# EasyCheck_rev1.net
KiCad netlist of a schematic drawn in EAGLE
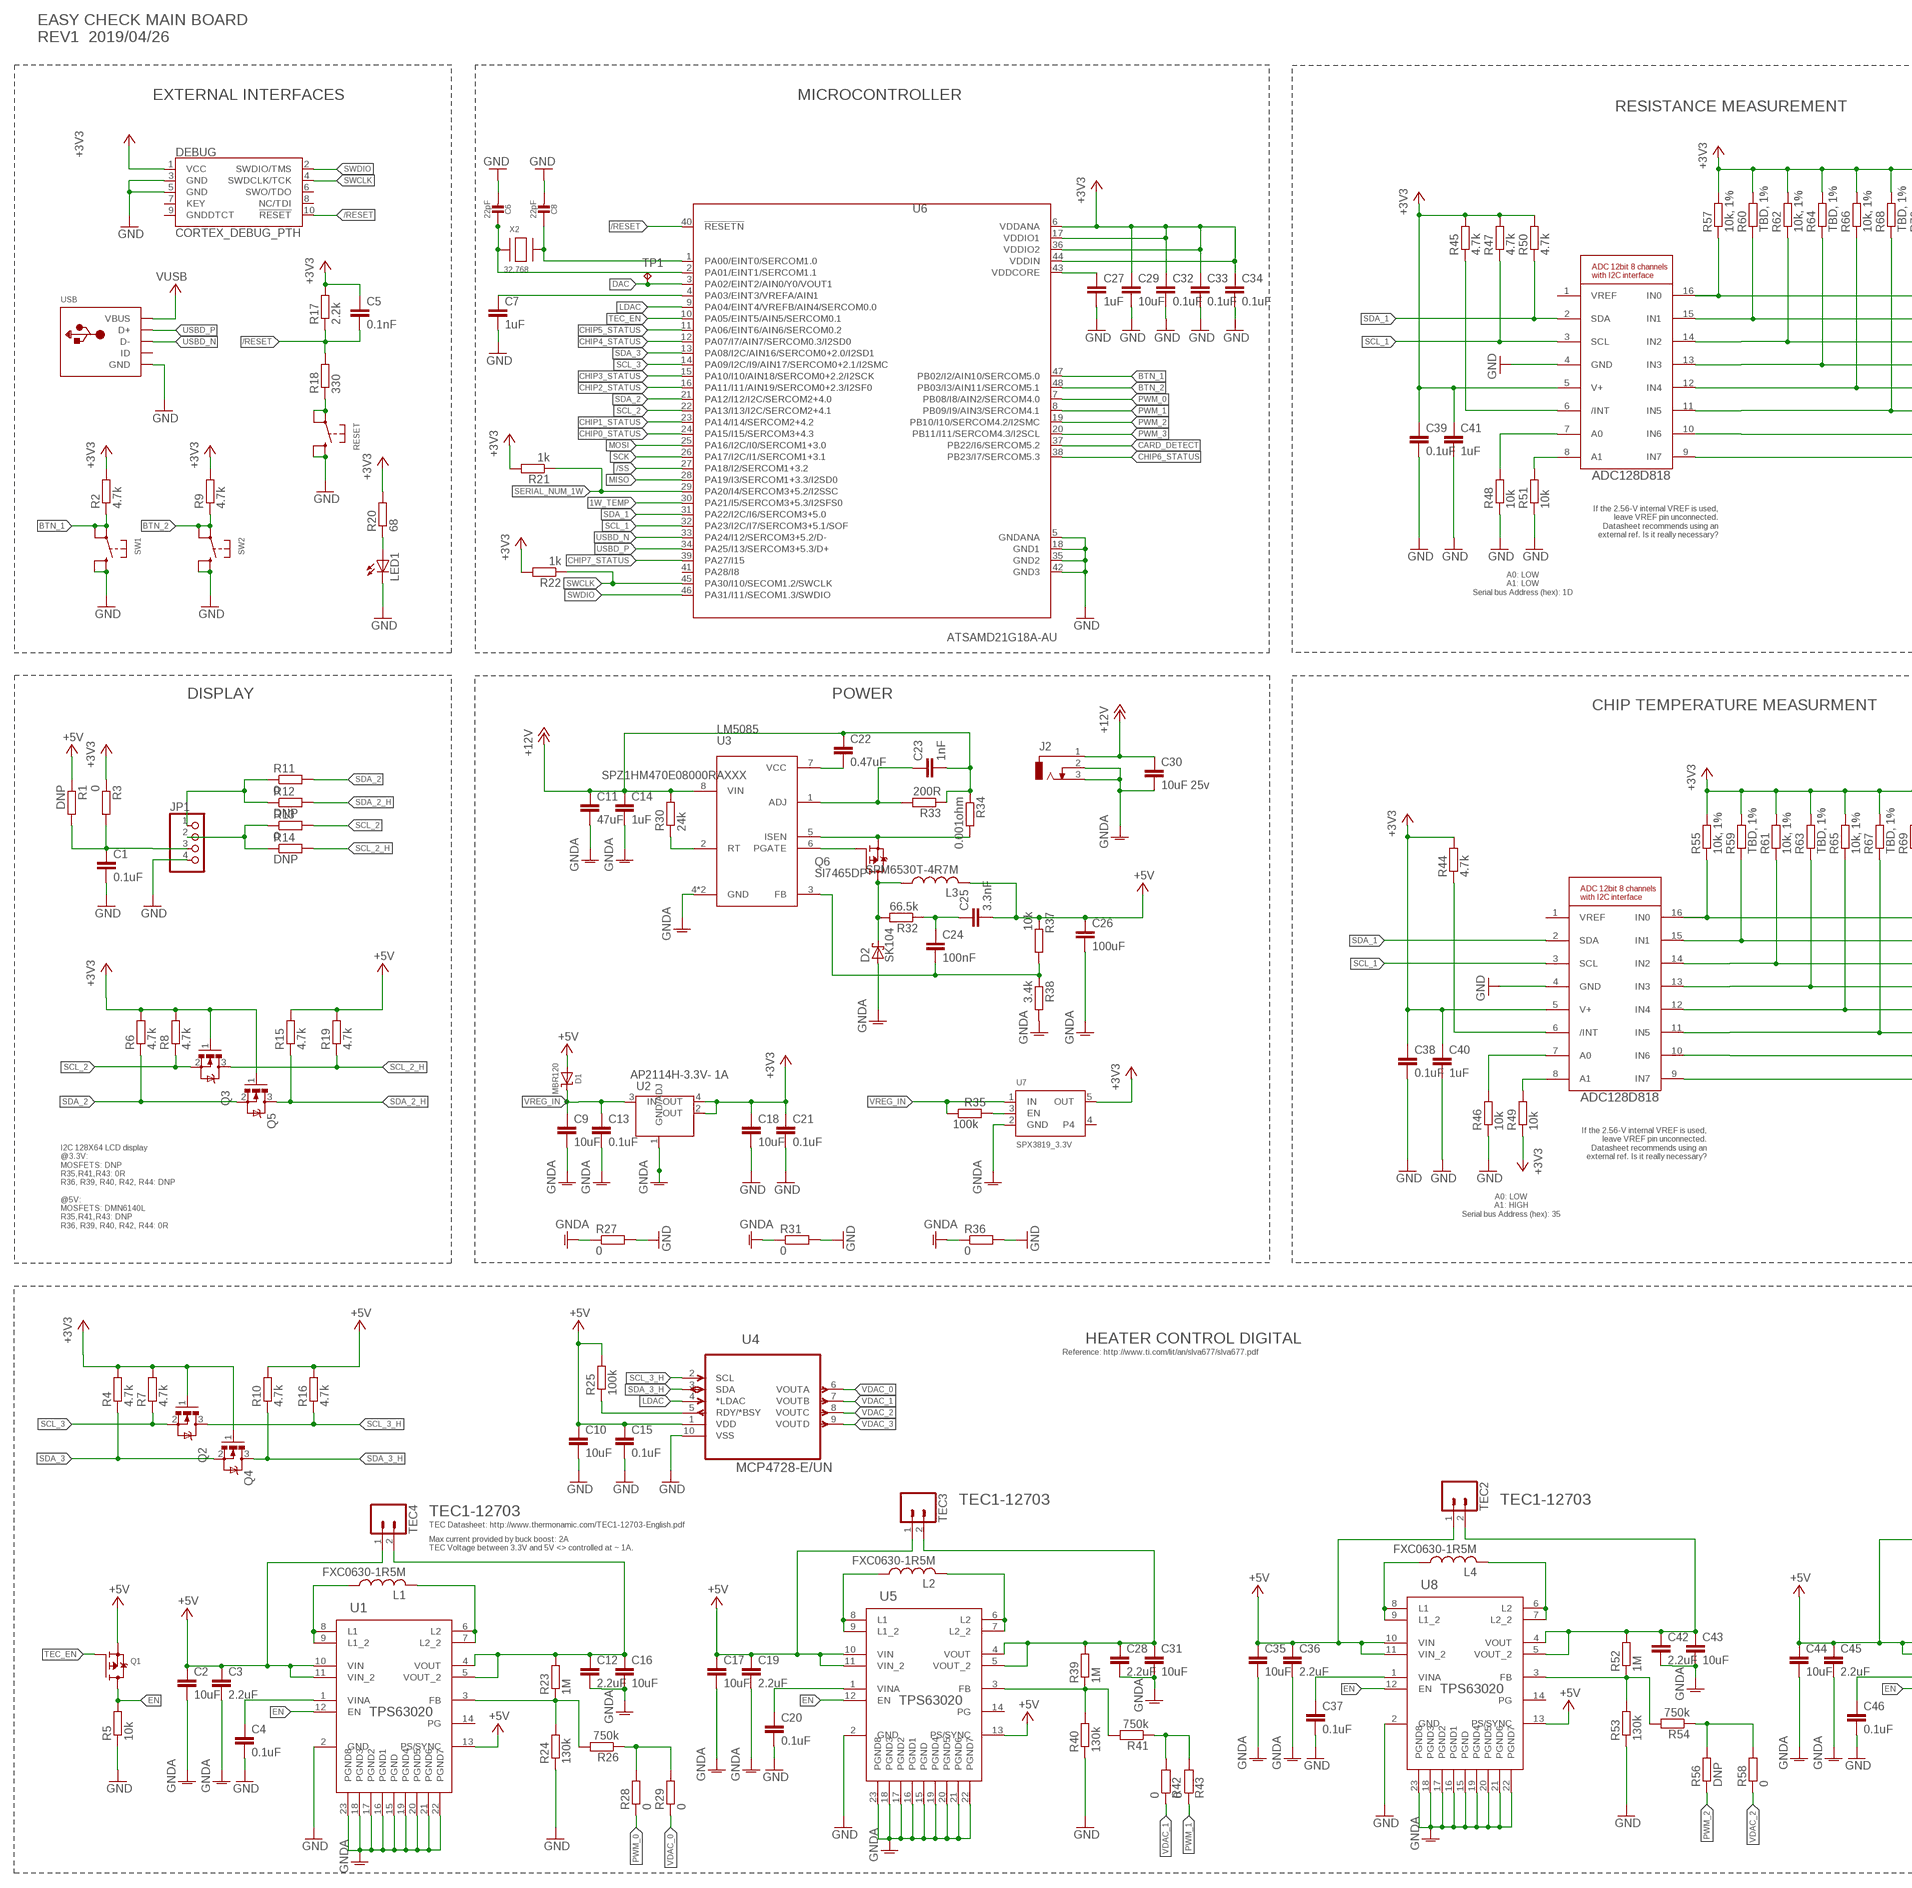
[diagram p0: schematic, sheet 1, part 1 of 2]
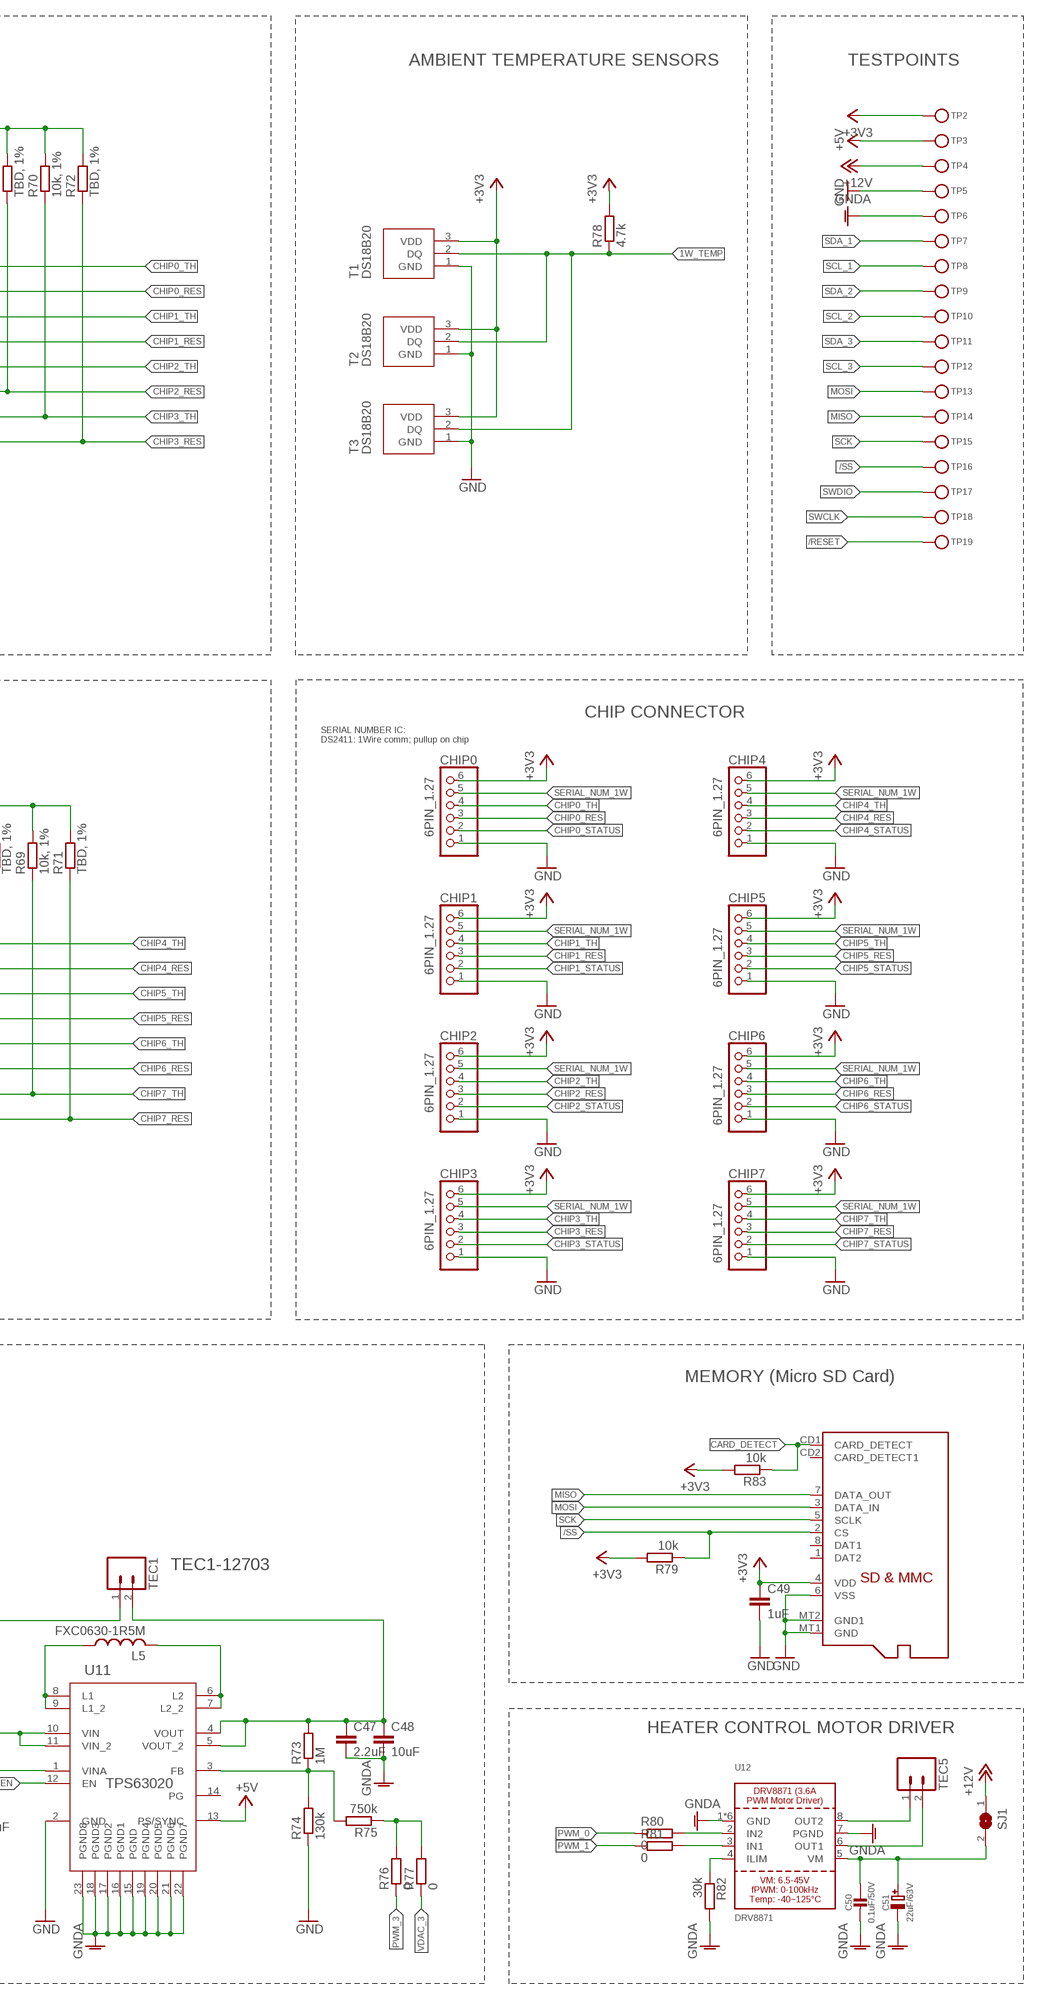
[diagram p1: schematic, sheet 1, part 2 of 2]

(export (version "E")
  (design (tool "Eeschema 10.0.6"))
  (components
    (comp (ref "C1")
      (value "0.1uF")
      (footprint "eagle-import:C0603")
      (libsource (lib "eagle-import") (part "C-EUC0603"))
    )
    (comp (ref "C2")
      (value "10uF")
      (footprint "eagle-import:C0805")
      (libsource (lib "eagle-import") (part "C-EUC0805"))
    )
    (comp (ref "C3")
      (value "2.2uF")
      (footprint "eagle-import:C0805")
      (libsource (lib "eagle-import") (part "C-EUC0805"))
    )
    (comp (ref "C4")
      (value "0.1uF")
      (footprint "eagle-import:C0603")
      (libsource (lib "eagle-import") (part "C-EUC0603"))
    )
    (comp (ref "C5")
      (value "0.1nF")
      (footprint "eagle-import:C0603")
      (libsource (lib "eagle-import") (part "C-EUC0603"))
    )
    (comp (ref "C6")
      (value "22pF")
      (footprint "eagle-import:0603-NO")
      (libsource (lib "eagle-import") (part "CAP_CERAMIC0603_NO"))
    )
    (comp (ref "C7")
      (value "1uF")
      (footprint "eagle-import:C0603")
      (libsource (lib "eagle-import") (part "C-EUC0603"))
    )
    (comp (ref "C8")
      (value "22pF")
      (footprint "eagle-import:0603-NO")
      (libsource (lib "eagle-import") (part "CAP_CERAMIC0603_NO"))
    )
    (comp (ref "C9")
      (value "10uF")
      (footprint "eagle-import:C0603")
      (libsource (lib "eagle-import") (part "C-EUC0603"))
    )
    (comp (ref "C10")
      (value "10uF")
      (footprint "eagle-import:C0603")
      (libsource (lib "eagle-import") (part "C-EUC0603"))
    )
    (comp (ref "C11")
      (value "47uF")
      (footprint "eagle-import:C1206")
      (libsource (lib "eagle-import") (part "C-EUC1206"))
    )
    (comp (ref "C12")
      (value "2.2uF")
      (footprint "eagle-import:C0805")
      (libsource (lib "eagle-import") (part "C-EUC0805"))
    )
    (comp (ref "C13")
      (value "0.1uF")
      (footprint "eagle-import:C0603")
      (libsource (lib "eagle-import") (part "C-EUC0603"))
    )
    (comp (ref "C14")
      (value "1uF")
      (footprint "eagle-import:C1206")
      (libsource (lib "eagle-import") (part "C-EUC1206"))
    )
    (comp (ref "C15")
      (value "0.1uF")
      (footprint "eagle-import:C0603")
      (libsource (lib "eagle-import") (part "C-EUC0603"))
    )
    (comp (ref "C16")
      (value "10uF")
      (footprint "eagle-import:C0805")
      (libsource (lib "eagle-import") (part "C-EUC0805"))
    )
    (comp (ref "C17")
      (value "10uF")
      (footprint "eagle-import:C0805")
      (libsource (lib "eagle-import") (part "C-EUC0805"))
    )
    (comp (ref "C18")
      (value "10uF")
      (footprint "eagle-import:C0603")
      (libsource (lib "eagle-import") (part "C-EUC0603"))
    )
    (comp (ref "C19")
      (value "2.2uF")
      (footprint "eagle-import:C0805")
      (libsource (lib "eagle-import") (part "C-EUC0805"))
    )
    (comp (ref "C20")
      (value "0.1uF")
      (footprint "eagle-import:C0603")
      (libsource (lib "eagle-import") (part "C-EUC0603"))
    )
    (comp (ref "C21")
      (value "0.1uF")
      (footprint "eagle-import:C0603")
      (libsource (lib "eagle-import") (part "C-EUC0603"))
    )
    (comp (ref "C22")
      (value "0.47uF")
      (footprint "eagle-import:C1206")
      (libsource (lib "eagle-import") (part "C-EUC1206"))
    )
    (comp (ref "C23")
      (value "1nF")
      (footprint "eagle-import:C0603")
      (libsource (lib "eagle-import") (part "C-EUC0603"))
    )
    (comp (ref "C24")
      (value "100nF")
      (footprint "eagle-import:C0603")
      (libsource (lib "eagle-import") (part "C-EUC0603"))
    )
    (comp (ref "C25")
      (value "3.3nF")
      (footprint "eagle-import:C0603")
      (libsource (lib "eagle-import") (part "C-EUC0603"))
    )
    (comp (ref "C26")
      (value "100uF")
      (footprint "eagle-import:C1206")
      (libsource (lib "eagle-import") (part "C-EUC1206"))
    )
    (comp (ref "C27")
      (value "1uF")
      (footprint "eagle-import:C0603")
      (libsource (lib "eagle-import") (part "C-EUC0603"))
    )
    (comp (ref "C28")
      (value "2.2uF")
      (footprint "eagle-import:C0805")
      (libsource (lib "eagle-import") (part "C-EUC0805"))
    )
    (comp (ref "C29")
      (value "10uF")
      (footprint "eagle-import:C0603")
      (libsource (lib "eagle-import") (part "C-EUC0603"))
    )
    (comp (ref "C30")
      (value "10uF 25v")
      (footprint "eagle-import:C1206")
      (libsource (lib "eagle-import") (part "C-EUC1206"))
    )
    (comp (ref "C31")
      (value "10uF")
      (footprint "eagle-import:C0805")
      (libsource (lib "eagle-import") (part "C-EUC0805"))
    )
    (comp (ref "C32")
      (value "0.1uF")
      (footprint "eagle-import:C0603")
      (libsource (lib "eagle-import") (part "C-EUC0603"))
    )
    (comp (ref "C33")
      (value "0.1uF")
      (footprint "eagle-import:C0603")
      (libsource (lib "eagle-import") (part "C-EUC0603"))
    )
    (comp (ref "C34")
      (value "0.1uF")
      (footprint "eagle-import:C0603")
      (libsource (lib "eagle-import") (part "C-EUC0603"))
    )
    (comp (ref "C35")
      (value "10uF")
      (footprint "eagle-import:C0603")
      (libsource (lib "eagle-import") (part "C-EUC0603"))
    )
    (comp (ref "C36")
      (value "2.2uF")
      (footprint "eagle-import:C0603")
      (libsource (lib "eagle-import") (part "C-EUC0603"))
    )
    (comp (ref "C37")
      (value "0.1uF")
      (footprint "eagle-import:C0603")
      (libsource (lib "eagle-import") (part "C-EUC0603"))
    )
    (comp (ref "C38")
      (value "0.1uF")
      (footprint "eagle-import:C0603")
      (libsource (lib "eagle-import") (part "C-EUC0603"))
    )
    (comp (ref "C39")
      (value "0.1uF")
      (footprint "eagle-import:C0603")
      (libsource (lib "eagle-import") (part "C-EUC0603"))
    )
    (comp (ref "C40")
      (value "1uF")
      (footprint "eagle-import:C0603")
      (libsource (lib "eagle-import") (part "C-EUC0603"))
    )
    (comp (ref "C41")
      (value "1uF")
      (footprint "eagle-import:C0603")
      (libsource (lib "eagle-import") (part "C-EUC0603"))
    )
    (comp (ref "C42")
      (value "2.2uF")
      (footprint "eagle-import:C0805")
      (libsource (lib "eagle-import") (part "C-EUC0805"))
    )
    (comp (ref "C43")
      (value "10uF")
      (footprint "eagle-import:C0805")
      (libsource (lib "eagle-import") (part "C-EUC0805"))
    )
    (comp (ref "C44")
      (value "10uF")
      (footprint "eagle-import:C0805")
      (libsource (lib "eagle-import") (part "C-EUC0805"))
    )
    (comp (ref "C45")
      (value "2.2uF")
      (footprint "eagle-import:C0805")
      (libsource (lib "eagle-import") (part "C-EUC0805"))
    )
    (comp (ref "C46")
      (value "0.1uF")
      (footprint "eagle-import:C0603")
      (libsource (lib "eagle-import") (part "C-EUC0603"))
    )
    (comp (ref "C47")
      (value "2.2uF")
      (footprint "eagle-import:C0805")
      (libsource (lib "eagle-import") (part "C-EUC0805"))
    )
    (comp (ref "C48")
      (value "10uF")
      (footprint "eagle-import:C0805")
      (libsource (lib "eagle-import") (part "C-EUC0805"))
    )
    (comp (ref "C49")
      (value "1uF")
      (footprint "eagle-import:C0603")
      (libsource (lib "eagle-import") (part "C-EUC0603"))
    )
    (comp (ref "C50")
      (value "0.1uF/50V")
      (footprint "eagle-import:0805-NO")
      (libsource (lib "eagle-import") (part "CAP_CERAMIC0805-NOOUTLINE"))
    )
    (comp (ref "C51")
      (value "22uF/63V")
      (footprint "eagle-import:PANASONIC_D")
      (libsource (lib "eagle-import") (part "CAP_ELECTROLYTICPANASONIC_D"))
    )
    (comp (ref "CHIP0")
      (value "6PIN_1.27")
      (footprint "eagle-import:6X1PIN_1.27")
      (libsource (lib "eagle-import") (part "6PIN_1.27"))
    )
    (comp (ref "CHIP1")
      (value "6PIN_1.27")
      (footprint "eagle-import:6X1PIN_1.27")
      (libsource (lib "eagle-import") (part "6PIN_1.27"))
    )
    (comp (ref "CHIP2")
      (value "6PIN_1.27")
      (footprint "eagle-import:6X1PIN_1.27")
      (libsource (lib "eagle-import") (part "6PIN_1.27"))
    )
    (comp (ref "CHIP3")
      (value "6PIN_1.27")
      (footprint "eagle-import:6X1PIN_1.27")
      (libsource (lib "eagle-import") (part "6PIN_1.27"))
    )
    (comp (ref "CHIP4")
      (value "6PIN_1.27")
      (footprint "eagle-import:6X1PIN_1.27")
      (libsource (lib "eagle-import") (part "6PIN_1.27"))
    )
    (comp (ref "CHIP5")
      (value "6PIN_1.27")
      (footprint "eagle-import:6X1PIN_1.27")
      (libsource (lib "eagle-import") (part "6PIN_1.27"))
    )
    (comp (ref "CHIP6")
      (value "6PIN_1.27")
      (footprint "eagle-import:6X1PIN_1.27")
      (libsource (lib "eagle-import") (part "6PIN_1.27"))
    )
    (comp (ref "CHIP7")
      (value "6PIN_1.27")
      (footprint "eagle-import:6X1PIN_1.27")
      (libsource (lib "eagle-import") (part "6PIN_1.27"))
    )
    (comp (ref "D1")
      (value "MBR120")
      (footprint "eagle-import:MICROBUILDER_SOD-123")
      (libsource (lib "eagle-import") (part "MICROBUILDER_DIODE-SCHOTTKYSOD-123"))
    )
    (comp (ref "D2")
      (value "SK104")
      (footprint "eagle-import:SK104")
      (libsource (lib "eagle-import") (part "SK104"))
    )
    (comp (ref "DEBUG")
      (value "CORTEX_DEBUG_PTH")
      (footprint "eagle-import:2X5-PTH-1.27MM")
      (libsource (lib "eagle-import") (part "CORTEX_DEBUG_PTH"))
    )
    (comp (ref "J2")
      (value "DCJ0303")
      (footprint "eagle-import:DCJ0303")
      (libsource (lib "eagle-import") (part "DCJ0303"))
    )
    (comp (ref "JP1")
      (value "PINHD-1X4")
      (footprint "eagle-import:1X04")
      (libsource (lib "eagle-import") (part "PINHD-1X4"))
    )
    (comp (ref "L1")
      (value "FXC0630-1R5M")
      (footprint "eagle-import:PIS2816")
      (libsource (lib "eagle-import") (part "L-USPIS2816"))
    )
    (comp (ref "L2")
      (value "FXC0630-1R5M")
      (footprint "eagle-import:PIS2816")
      (libsource (lib "eagle-import") (part "L-USPIS2816"))
    )
    (comp (ref "L3")
      (value "SPM6530T-4R7M")
      (footprint "eagle-import:SPM6530T-4R7M")
      (libsource (lib "eagle-import") (part "SPM6530T-4R7M"))
    )
    (comp (ref "L4")
      (value "FXC0630-1R5M")
      (footprint "eagle-import:PIS2816")
      (libsource (lib "eagle-import") (part "L-USPIS2816"))
    )
    (comp (ref "L5")
      (value "FXC0630-1R5M")
      (footprint "eagle-import:PIS2816")
      (libsource (lib "eagle-import") (part "L-USPIS2816"))
    )
    (comp (ref "LED1")
      (value "LEDCHIPLED_0603")
      (footprint "eagle-import:CHIPLED_0603")
      (libsource (lib "eagle-import") (part "LEDCHIPLED_0603"))
    )
    (comp (ref "Q1")
      (value "MICROBUILDER_MOSFET-P")
      (footprint "eagle-import:MICROBUILDER_SOT23-R")
      (libsource (lib "eagle-import") (part "MICROBUILDER_MOSFET-P"))
    )
    (comp (ref "Q2")
      (value "DMN6140L")
      (footprint "eagle-import:SOT91P240X110-3N")
      (libsource (lib "eagle-import") (part "DMN6140L"))
    )
    (comp (ref "Q3")
      (value "DMN6140L")
      (footprint "eagle-import:SOT91P240X110-3N")
      (libsource (lib "eagle-import") (part "DMN6140L"))
    )
    (comp (ref "Q4")
      (value "DMN6140L")
      (footprint "eagle-import:SOT91P240X110-3N")
      (libsource (lib "eagle-import") (part "DMN6140L"))
    )
    (comp (ref "Q5")
      (value "DMN6140L")
      (footprint "eagle-import:SOT91P240X110-3N")
      (libsource (lib "eagle-import") (part "DMN6140L"))
    )
    (comp (ref "Q6")
      (value "SI7465DP")
      (footprint "eagle-import:SI7465")
      (libsource (lib "eagle-import") (part "SI7465DP"))
    )
    (comp (ref "R1")
      (value "DNP")
      (footprint "eagle-import:R0603")
      (libsource (lib "eagle-import") (part "R-EU_R0603"))
    )
    (comp (ref "R2")
      (value "4.7k")
      (footprint "eagle-import:R0603")
      (libsource (lib "eagle-import") (part "R-EU_R0603"))
    )
    (comp (ref "R3")
      (value "0")
      (footprint "eagle-import:R0603")
      (libsource (lib "eagle-import") (part "R-EU_R0603"))
    )
    (comp (ref "R4")
      (value "4.7k")
      (footprint "eagle-import:R0603")
      (libsource (lib "eagle-import") (part "R-EU_R0603"))
    )
    (comp (ref "R5")
      (value "10k")
      (footprint "eagle-import:R0603")
      (libsource (lib "eagle-import") (part "R-EU_R0603"))
    )
    (comp (ref "R6")
      (value "4.7k")
      (footprint "eagle-import:R0603")
      (libsource (lib "eagle-import") (part "R-EU_R0603"))
    )
    (comp (ref "R7")
      (value "4.7k")
      (footprint "eagle-import:R0603")
      (libsource (lib "eagle-import") (part "R-EU_R0603"))
    )
    (comp (ref "R8")
      (value "4.7k")
      (footprint "eagle-import:R0603")
      (libsource (lib "eagle-import") (part "R-EU_R0603"))
    )
    (comp (ref "R9")
      (value "4.7k")
      (footprint "eagle-import:R0603")
      (libsource (lib "eagle-import") (part "R-EU_R0603"))
    )
    (comp (ref "R10")
      (value "4.7k")
      (footprint "eagle-import:R0603")
      (libsource (lib "eagle-import") (part "R-EU_R0603"))
    )
    (comp (ref "R11")
      (value "0")
      (footprint "eagle-import:R0603")
      (libsource (lib "eagle-import") (part "R-EU_R0603"))
    )
    (comp (ref "R12")
      (value "DNP")
      (footprint "eagle-import:R0603")
      (libsource (lib "eagle-import") (part "R-EU_R0603"))
    )
    (comp (ref "R13")
      (value "0")
      (footprint "eagle-import:R0603")
      (libsource (lib "eagle-import") (part "R-EU_R0603"))
    )
    (comp (ref "R14")
      (value "DNP")
      (footprint "eagle-import:R0603")
      (libsource (lib "eagle-import") (part "R-EU_R0603"))
    )
    (comp (ref "R15")
      (value "4.7k")
      (footprint "eagle-import:R0603")
      (libsource (lib "eagle-import") (part "R-EU_R0603"))
    )
    (comp (ref "R16")
      (value "4.7k")
      (footprint "eagle-import:R0603")
      (libsource (lib "eagle-import") (part "R-EU_R0603"))
    )
    (comp (ref "R17")
      (value "2.2k")
      (footprint "eagle-import:R0603")
      (libsource (lib "eagle-import") (part "R-EU_R0603"))
    )
    (comp (ref "R18")
      (value "330")
      (footprint "eagle-import:R0603")
      (libsource (lib "eagle-import") (part "R-EU_R0603"))
    )
    (comp (ref "R19")
      (value "4.7k")
      (footprint "eagle-import:R0603")
      (libsource (lib "eagle-import") (part "R-EU_R0603"))
    )
    (comp (ref "R20")
      (value "68")
      (footprint "eagle-import:R0603")
      (libsource (lib "eagle-import") (part "R-EU_R0603"))
    )
    (comp (ref "R21")
      (value "1k")
      (footprint "eagle-import:R0603")
      (libsource (lib "eagle-import") (part "R-EU_R0603"))
    )
    (comp (ref "R22")
      (value "1k")
      (footprint "eagle-import:R0603")
      (libsource (lib "eagle-import") (part "R-EU_R0603"))
    )
    (comp (ref "R23")
      (value "1M")
      (footprint "eagle-import:R0603")
      (libsource (lib "eagle-import") (part "R-EU_R0603"))
    )
    (comp (ref "R24")
      (value "130k")
      (footprint "eagle-import:R0603")
      (libsource (lib "eagle-import") (part "R-EU_R0603"))
    )
    (comp (ref "R25")
      (value "100k")
      (footprint "eagle-import:R0603")
      (libsource (lib "eagle-import") (part "R-EU_R0603"))
    )
    (comp (ref "R26")
      (value "750k")
      (footprint "eagle-import:R0603")
      (libsource (lib "eagle-import") (part "R-EU_R0603"))
    )
    (comp (ref "R27")
      (value "0")
      (footprint "eagle-import:R0603")
      (libsource (lib "eagle-import") (part "R-EU_R0603"))
    )
    (comp (ref "R28")
      (value "0")
      (footprint "eagle-import:R0603")
      (libsource (lib "eagle-import") (part "R-EU_R0603"))
    )
    (comp (ref "R29")
      (value "0")
      (footprint "eagle-import:R0603")
      (libsource (lib "eagle-import") (part "R-EU_R0603"))
    )
    (comp (ref "R30")
      (value "24k")
      (footprint "eagle-import:R0603")
      (libsource (lib "eagle-import") (part "R-EU_R0603"))
    )
    (comp (ref "R31")
      (value "0")
      (footprint "eagle-import:R0603")
      (libsource (lib "eagle-import") (part "R-EU_R0603"))
    )
    (comp (ref "R32")
      (value "66.5k")
      (footprint "eagle-import:R0603")
      (libsource (lib "eagle-import") (part "R-EU_R0603"))
    )
    (comp (ref "R33")
      (value "200R")
      (footprint "eagle-import:R0603")
      (libsource (lib "eagle-import") (part "R-EU_R0603"))
    )
    (comp (ref "R34")
      (value "0.001ohm")
      (footprint "eagle-import:R1206")
      (libsource (lib "eagle-import") (part "R-EU_R1206"))
    )
    (comp (ref "R35")
      (value "100k")
      (footprint "eagle-import:R0603")
      (libsource (lib "eagle-import") (part "R-EU_R0603"))
    )
    (comp (ref "R36")
      (value "0")
      (footprint "eagle-import:R0603")
      (libsource (lib "eagle-import") (part "R-EU_R0603"))
    )
    (comp (ref "R37")
      (value "10k")
      (footprint "eagle-import:R0603")
      (libsource (lib "eagle-import") (part "R-EU_R0603"))
    )
    (comp (ref "R38")
      (value "3.4k")
      (footprint "eagle-import:R0603")
      (libsource (lib "eagle-import") (part "R-EU_R0603"))
    )
    (comp (ref "R39")
      (value "1M")
      (footprint "eagle-import:R0603")
      (libsource (lib "eagle-import") (part "R-EU_R0603"))
    )
    (comp (ref "R40")
      (value "130k")
      (footprint "eagle-import:R0603")
      (libsource (lib "eagle-import") (part "R-EU_R0603"))
    )
    (comp (ref "R41")
      (value "750k")
      (footprint "eagle-import:R0603")
      (libsource (lib "eagle-import") (part "R-EU_R0603"))
    )
    (comp (ref "R42")
      (value "0")
      (footprint "eagle-import:R0603")
      (libsource (lib "eagle-import") (part "R-EU_R0603"))
    )
    (comp (ref "R43")
      (value "0")
      (footprint "eagle-import:R0603")
      (libsource (lib "eagle-import") (part "R-EU_R0603"))
    )
    (comp (ref "R44")
      (value "4.7k")
      (footprint "eagle-import:R0603")
      (libsource (lib "eagle-import") (part "R-EU_R0603"))
    )
    (comp (ref "R45")
      (value "4.7k")
      (footprint "eagle-import:R0603")
      (libsource (lib "eagle-import") (part "R-EU_R0603"))
    )
    (comp (ref "R46")
      (value "10k")
      (footprint "eagle-import:R0603")
      (libsource (lib "eagle-import") (part "R-EU_R0603"))
    )
    (comp (ref "R47")
      (value "4.7k")
      (footprint "eagle-import:R0603")
      (libsource (lib "eagle-import") (part "R-EU_R0603"))
    )
    (comp (ref "R48")
      (value "10k")
      (footprint "eagle-import:R0603")
      (libsource (lib "eagle-import") (part "R-EU_R0603"))
    )
    (comp (ref "R49")
      (value "10k")
      (footprint "eagle-import:R0603")
      (libsource (lib "eagle-import") (part "R-EU_R0603"))
    )
    (comp (ref "R50")
      (value "4.7k")
      (footprint "eagle-import:R0603")
      (libsource (lib "eagle-import") (part "R-EU_R0603"))
    )
    (comp (ref "R51")
      (value "10k")
      (footprint "eagle-import:R0603")
      (libsource (lib "eagle-import") (part "R-EU_R0603"))
    )
    (comp (ref "R52")
      (value "1M")
      (footprint "eagle-import:R0603")
      (libsource (lib "eagle-import") (part "R-EU_R0603"))
    )
    (comp (ref "R53")
      (value "130k")
      (footprint "eagle-import:R0603")
      (libsource (lib "eagle-import") (part "R-EU_R0603"))
    )
    (comp (ref "R54")
      (value "750k")
      (footprint "eagle-import:R0603")
      (libsource (lib "eagle-import") (part "R-EU_R0603"))
    )
    (comp (ref "R55")
      (value "10k, 1%")
      (footprint "eagle-import:R0603")
      (libsource (lib "eagle-import") (part "R-EU_R0603"))
    )
    (comp (ref "R56")
      (value "DNP")
      (footprint "eagle-import:R0603")
      (libsource (lib "eagle-import") (part "R-EU_R0603"))
    )
    (comp (ref "R57")
      (value "10k, 1%")
      (footprint "eagle-import:R0603")
      (libsource (lib "eagle-import") (part "R-EU_R0603"))
    )
    (comp (ref "R58")
      (value "0")
      (footprint "eagle-import:R0603")
      (libsource (lib "eagle-import") (part "R-EU_R0603"))
    )
    (comp (ref "R59")
      (value "TBD, 1%")
      (footprint "eagle-import:R0603")
      (libsource (lib "eagle-import") (part "R-EU_R0603"))
    )
    (comp (ref "R60")
      (value "TBD, 1%")
      (footprint "eagle-import:R0603")
      (libsource (lib "eagle-import") (part "R-EU_R0603"))
    )
    (comp (ref "R61")
      (value "10k, 1%")
      (footprint "eagle-import:R0603")
      (libsource (lib "eagle-import") (part "R-EU_R0603"))
    )
    (comp (ref "R62")
      (value "10k, 1%")
      (footprint "eagle-import:R0603")
      (libsource (lib "eagle-import") (part "R-EU_R0603"))
    )
    (comp (ref "R63")
      (value "TBD, 1%")
      (footprint "eagle-import:R0603")
      (libsource (lib "eagle-import") (part "R-EU_R0603"))
    )
    (comp (ref "R64")
      (value "TBD, 1%")
      (footprint "eagle-import:R0603")
      (libsource (lib "eagle-import") (part "R-EU_R0603"))
    )
    (comp (ref "R65")
      (value "10k, 1%")
      (footprint "eagle-import:R0603")
      (libsource (lib "eagle-import") (part "R-EU_R0603"))
    )
    (comp (ref "R66")
      (value "10k, 1%")
      (footprint "eagle-import:R0603")
      (libsource (lib "eagle-import") (part "R-EU_R0603"))
    )
    (comp (ref "R67")
      (value "TBD, 1%")
      (footprint "eagle-import:R0603")
      (libsource (lib "eagle-import") (part "R-EU_R0603"))
    )
    (comp (ref "R68")
      (value "TBD, 1%")
      (footprint "eagle-import:R0603")
      (libsource (lib "eagle-import") (part "R-EU_R0603"))
    )
    (comp (ref "R69")
      (value "10k, 1%")
      (footprint "eagle-import:R0603")
      (libsource (lib "eagle-import") (part "R-EU_R0603"))
    )
    (comp (ref "R70")
      (value "10k, 1%")
      (footprint "eagle-import:R0603")
      (libsource (lib "eagle-import") (part "R-EU_R0603"))
    )
    (comp (ref "R71")
      (value "TBD, 1%")
      (footprint "eagle-import:R0603")
      (libsource (lib "eagle-import") (part "R-EU_R0603"))
    )
    (comp (ref "R72")
      (value "TBD, 1%")
      (footprint "eagle-import:R0603")
      (libsource (lib "eagle-import") (part "R-EU_R0603"))
    )
    (comp (ref "R73")
      (value "1M")
      (footprint "eagle-import:R0603")
      (libsource (lib "eagle-import") (part "R-EU_R0603"))
    )
    (comp (ref "R74")
      (value "130k")
      (footprint "eagle-import:R0603")
      (libsource (lib "eagle-import") (part "R-EU_R0603"))
    )
    (comp (ref "R75")
      (value "750k")
      (footprint "eagle-import:R0603")
      (libsource (lib "eagle-import") (part "R-EU_R0603"))
    )
    (comp (ref "R76")
      (value "0")
      (footprint "eagle-import:R0603")
      (libsource (lib "eagle-import") (part "R-EU_R0603"))
    )
    (comp (ref "R77")
      (value "0")
      (footprint "eagle-import:R0603")
      (libsource (lib "eagle-import") (part "R-EU_R0603"))
    )
    (comp (ref "R78")
      (value "4.7k")
      (footprint "eagle-import:R0603")
      (libsource (lib "eagle-import") (part "R-EU_R0603"))
    )
    (comp (ref "R79")
      (value "10k")
      (footprint "eagle-import:R0603")
      (libsource (lib "eagle-import") (part "R-EU_R0603"))
    )
    (comp (ref "R80")
      (value "0")
      (footprint "eagle-import:R0603")
      (libsource (lib "eagle-import") (part "R-EU_R0603"))
    )
    (comp (ref "R81")
      (value "0")
      (footprint "eagle-import:R0603")
      (libsource (lib "eagle-import") (part "R-EU_R0603"))
    )
    (comp (ref "R82")
      (value "30k")
      (footprint "eagle-import:R0603")
      (libsource (lib "eagle-import") (part "R-EU_R0603"))
    )
    (comp (ref "R83")
      (value "10k")
      (footprint "eagle-import:R0603")
      (libsource (lib "eagle-import") (part "R-EU_R0603"))
    )
    (comp (ref "RESET")
      (value "MICROBUILDER_SWITCH_TACT_SMT_EVQQ2_SMALL")
      (footprint "eagle-import:MICROBUILDER_EVQ-Q2_SMALLER")
      (libsource (lib "eagle-import") (part "MICROBUILDER_SWITCH_TACT_SMT_EVQQ2_SMALL"))
    )
    (comp (ref "SD1")
      (value "MICROSD")
      (footprint "eagle-import:MICROSD")
      (libsource (lib "eagle-import") (part "MICROSD"))
    )
    (comp (ref "SJ1")
      (value "SJW")
      (footprint "eagle-import:SJW")
      (libsource (lib "eagle-import") (part "SJW"))
    )
    (comp (ref "SW1")
      (value "MICROBUILDER_SWITCH_TACT_SMT_EVQQ2_SMALL")
      (footprint "eagle-import:MICROBUILDER_EVQ-Q2_SMALLER")
      (libsource (lib "eagle-import") (part "MICROBUILDER_SWITCH_TACT_SMT_EVQQ2_SMALL"))
    )
    (comp (ref "SW2")
      (value "MICROBUILDER_SWITCH_TACT_SMT_EVQQ2_SMALL")
      (footprint "eagle-import:MICROBUILDER_EVQ-Q2_SMALLER")
      (libsource (lib "eagle-import") (part "MICROBUILDER_SWITCH_TACT_SMT_EVQQ2_SMALL"))
    )
    (comp (ref "T1")
      (value "DS18B20")
      (footprint "eagle-import:TO92")
      (libsource (lib "eagle-import") (part "DS18B20"))
    )
    (comp (ref "T2")
      (value "DS18B20")
      (footprint "eagle-import:TO92")
      (libsource (lib "eagle-import") (part "DS18B20"))
    )
    (comp (ref "T3")
      (value "DS18B20")
      (footprint "eagle-import:TO92")
      (libsource (lib "eagle-import") (part "DS18B20"))
    )
    (comp (ref "TEC1")
      (value "SPARKFUN-CONNECTORS_M025MM")
      (footprint "eagle-import:SPARKFUN-CONNECTORS_SCREWTERMINAL-5MM-2$1")
      (libsource (lib "eagle-import") (part "SPARKFUN-CONNECTORS_M025MM"))
    )
    (comp (ref "TEC2")
      (value "SPARKFUN-CONNECTORS_M025MM")
      (footprint "eagle-import:SPARKFUN-CONNECTORS_SCREWTERMINAL-5MM-2$1")
      (libsource (lib "eagle-import") (part "SPARKFUN-CONNECTORS_M025MM"))
    )
    (comp (ref "TEC3")
      (value "SPARKFUN-CONNECTORS_M025MM")
      (footprint "eagle-import:SPARKFUN-CONNECTORS_SCREWTERMINAL-5MM-2$1")
      (libsource (lib "eagle-import") (part "SPARKFUN-CONNECTORS_M025MM"))
    )
    (comp (ref "TEC4")
      (value "SPARKFUN-CONNECTORS_M025MM")
      (footprint "eagle-import:SPARKFUN-CONNECTORS_SCREWTERMINAL-5MM-2$1")
      (libsource (lib "eagle-import") (part "SPARKFUN-CONNECTORS_M025MM"))
    )
    (comp (ref "TEC5")
      (value "SPARKFUN-CONNECTORS_M025MM")
      (footprint "eagle-import:SPARKFUN-CONNECTORS_SCREWTERMINAL-5MM-2$1")
      (libsource (lib "eagle-import") (part "SPARKFUN-CONNECTORS_M025MM"))
    )
    (comp (ref "TP1")
      (value "TPPAD1-17")
      (footprint "eagle-import:P1-17")
      (libsource (lib "eagle-import") (part "TPPAD1-17"))
    )
    (comp (ref "TP2")
      (value "MICROBUILDER_TESTPOINTROUND1.5MM")
      (footprint "eagle-import:MICROBUILDER_TESTPOINT_ROUND_1.5MM")
      (libsource (lib "eagle-import") (part "MICROBUILDER_TESTPOINTROUND1.5MM"))
    )
    (comp (ref "TP3")
      (value "MICROBUILDER_TESTPOINTROUND1.5MM")
      (footprint "eagle-import:MICROBUILDER_TESTPOINT_ROUND_1.5MM")
      (libsource (lib "eagle-import") (part "MICROBUILDER_TESTPOINTROUND1.5MM"))
    )
    (comp (ref "TP4")
      (value "MICROBUILDER_TESTPOINTROUND1.5MM")
      (footprint "eagle-import:MICROBUILDER_TESTPOINT_ROUND_1.5MM")
      (libsource (lib "eagle-import") (part "MICROBUILDER_TESTPOINTROUND1.5MM"))
    )
    (comp (ref "TP5")
      (value "MICROBUILDER_TESTPOINTROUND1.5MM")
      (footprint "eagle-import:MICROBUILDER_TESTPOINT_ROUND_1.5MM")
      (libsource (lib "eagle-import") (part "MICROBUILDER_TESTPOINTROUND1.5MM"))
    )
    (comp (ref "TP6")
      (value "MICROBUILDER_TESTPOINTROUND1.5MM")
      (footprint "eagle-import:MICROBUILDER_TESTPOINT_ROUND_1.5MM")
      (libsource (lib "eagle-import") (part "MICROBUILDER_TESTPOINTROUND1.5MM"))
    )
    (comp (ref "TP7")
      (value "MICROBUILDER_TESTPOINTROUND1.5MM")
      (footprint "eagle-import:MICROBUILDER_TESTPOINT_ROUND_1.5MM")
      (libsource (lib "eagle-import") (part "MICROBUILDER_TESTPOINTROUND1.5MM"))
    )
    (comp (ref "TP8")
      (value "MICROBUILDER_TESTPOINTROUND1.5MM")
      (footprint "eagle-import:MICROBUILDER_TESTPOINT_ROUND_1.5MM")
      (libsource (lib "eagle-import") (part "MICROBUILDER_TESTPOINTROUND1.5MM"))
    )
    (comp (ref "TP9")
      (value "MICROBUILDER_TESTPOINTROUND1.5MM")
      (footprint "eagle-import:MICROBUILDER_TESTPOINT_ROUND_1.5MM")
      (libsource (lib "eagle-import") (part "MICROBUILDER_TESTPOINTROUND1.5MM"))
    )
    (comp (ref "TP10")
      (value "MICROBUILDER_TESTPOINTROUND1.5MM")
      (footprint "eagle-import:MICROBUILDER_TESTPOINT_ROUND_1.5MM")
      (libsource (lib "eagle-import") (part "MICROBUILDER_TESTPOINTROUND1.5MM"))
    )
    (comp (ref "TP11")
      (value "MICROBUILDER_TESTPOINTROUND1.5MM")
      (footprint "eagle-import:MICROBUILDER_TESTPOINT_ROUND_1.5MM")
      (libsource (lib "eagle-import") (part "MICROBUILDER_TESTPOINTROUND1.5MM"))
    )
    (comp (ref "TP12")
      (value "MICROBUILDER_TESTPOINTROUND1.5MM")
      (footprint "eagle-import:MICROBUILDER_TESTPOINT_ROUND_1.5MM")
      (libsource (lib "eagle-import") (part "MICROBUILDER_TESTPOINTROUND1.5MM"))
    )
    (comp (ref "TP13")
      (value "MICROBUILDER_TESTPOINTROUND1.5MM")
      (footprint "eagle-import:MICROBUILDER_TESTPOINT_ROUND_1.5MM")
      (libsource (lib "eagle-import") (part "MICROBUILDER_TESTPOINTROUND1.5MM"))
    )
    (comp (ref "TP14")
      (value "MICROBUILDER_TESTPOINTROUND1.5MM")
      (footprint "eagle-import:MICROBUILDER_TESTPOINT_ROUND_1.5MM")
      (libsource (lib "eagle-import") (part "MICROBUILDER_TESTPOINTROUND1.5MM"))
    )
    (comp (ref "TP15")
      (value "MICROBUILDER_TESTPOINTROUND1.5MM")
      (footprint "eagle-import:MICROBUILDER_TESTPOINT_ROUND_1.5MM")
      (libsource (lib "eagle-import") (part "MICROBUILDER_TESTPOINTROUND1.5MM"))
    )
    (comp (ref "TP16")
      (value "MICROBUILDER_TESTPOINTROUND1.5MM")
      (footprint "eagle-import:MICROBUILDER_TESTPOINT_ROUND_1.5MM")
      (libsource (lib "eagle-import") (part "MICROBUILDER_TESTPOINTROUND1.5MM"))
    )
    (comp (ref "TP17")
      (value "MICROBUILDER_TESTPOINTROUND1.5MM")
      (footprint "eagle-import:MICROBUILDER_TESTPOINT_ROUND_1.5MM")
      (libsource (lib "eagle-import") (part "MICROBUILDER_TESTPOINTROUND1.5MM"))
    )
    (comp (ref "TP18")
      (value "MICROBUILDER_TESTPOINTROUND1.5MM")
      (footprint "eagle-import:MICROBUILDER_TESTPOINT_ROUND_1.5MM")
      (libsource (lib "eagle-import") (part "MICROBUILDER_TESTPOINTROUND1.5MM"))
    )
    (comp (ref "TP19")
      (value "MICROBUILDER_TESTPOINTROUND1.5MM")
      (footprint "eagle-import:MICROBUILDER_TESTPOINT_ROUND_1.5MM")
      (libsource (lib "eagle-import") (part "MICROBUILDER_TESTPOINTROUND1.5MM"))
    )
    (comp (ref "U1")
      (value "TPS63020")
      (footprint "eagle-import:QFN14-3X4MM")
      (fields (field (name "MF") "Texas Instruments"))
      (libsource (lib "eagle-import") (part "TPS63020"))
    )
    (comp (ref "U2")
      (value "AP2114H-3.3V- 1A")
      (footprint "eagle-import:GEN_COMP_SOT223")
      (libsource (lib "eagle-import") (part "GEN_COMP_LINEAR_MC33269ST"))
    )
    (comp (ref "U3")
      (value "LM5085")
      (footprint "eagle-import:LM5085")
      (libsource (lib "eagle-import") (part "LM5085"))
    )
    (comp (ref "U4")
      (value "MCP4728-E/UN")
      (footprint "eagle-import:SOP50P490X110-10N")
      (libsource (lib "eagle-import") (part "MCP4728-E/UN"))
    )
    (comp (ref "U5")
      (value "TPS63020")
      (footprint "eagle-import:QFN14-3X4MM")
      (fields (field (name "MF") "Texas Instruments"))
      (libsource (lib "eagle-import") (part "TPS63020"))
    )
    (comp (ref "U6")
      (value "ATSAMD21G18A-AU")
      (footprint "eagle-import:QFP50P900X900X120-48N")
      (fields (field (name "MF") "Microchip"))
      (libsource (lib "eagle-import") (part "ATSAMD21G18A-AU"))
    )
    (comp (ref "U7")
      (value "SPX3819_3.3V")
      (footprint "eagle-import:MICROBUILDER_SOT23-5")
      (libsource (lib "eagle-import") (part "MICROBUILDER_VREG_SOT23-5"))
    )
    (comp (ref "U8")
      (value "TPS63020")
      (footprint "eagle-import:QFN14-3X4MM")
      (fields (field (name "MF") "Texas Instruments"))
      (libsource (lib "eagle-import") (part "TPS63020"))
    )
    (comp (ref "U9")
      (value "LMD128D818")
      (footprint "eagle-import:ADC128D818")
      (libsource (lib "eagle-import") (part "LMD128D818"))
    )
    (comp (ref "U10")
      (value "LMD128D818")
      (footprint "eagle-import:ADC128D818")
      (libsource (lib "eagle-import") (part "LMD128D818"))
    )
    (comp (ref "U11")
      (value "TPS63020")
      (footprint "eagle-import:QFN14-3X4MM")
      (fields (field (name "MF") "Texas Instruments"))
      (libsource (lib "eagle-import") (part "TPS63020"))
    )
    (comp (ref "U12")
      (value "DRV8871")
      (footprint "eagle-import:HSOP8")
      (libsource (lib "eagle-import") (part "DRV8871"))
    )
    (comp (ref "USB")
      (value "MICROBUILDER_USB_MICRO_20329_V2")
      (footprint "eagle-import:MICROBUILDER_4UCONN_20329_V2")
      (libsource (lib "eagle-import") (part "MICROBUILDER_USB_MICRO_20329_V2"))
    )
    (comp (ref "X2")
      (value "32.768")
      (footprint "eagle-import:XTAL3215")
      (libsource (lib "eagle-import") (part "XTAL-3.2X1.5"))
    )
  )
  (nets
    (net (code "1") (name "+3V3") (class "Default")
      (node (ref "C18") (pin "1") (pinfunction "1_1") (pintype "passive"))
      (node (ref "C21") (pin "1") (pinfunction "1_1") (pintype "passive"))
      (node (ref "C29") (pin "1") (pinfunction "1_1") (pintype "passive"))
      (node (ref "C32") (pin "1") (pinfunction "1_1") (pintype "passive"))
      (node (ref "C33") (pin "1") (pinfunction "1_1") (pintype "passive"))
      (node (ref "C34") (pin "1") (pinfunction "1_1") (pintype "passive"))
      (node (ref "C38") (pin "1") (pinfunction "1_1") (pintype "passive"))
      (node (ref "C39") (pin "1") (pinfunction "1_1") (pintype "passive"))
      (node (ref "C40") (pin "1") (pinfunction "1_1") (pintype "passive"))
      (node (ref "C41") (pin "1") (pinfunction "1_1") (pintype "passive"))
      (node (ref "C49") (pin "1") (pinfunction "1_1") (pintype "passive"))
      (node (ref "C5") (pin "1") (pinfunction "1_1") (pintype "passive"))
      (node (ref "CHIP0") (pin "6") (pinfunction "6_6") (pintype "passive"))
      (node (ref "CHIP1") (pin "6") (pinfunction "6_6") (pintype "passive"))
      (node (ref "CHIP2") (pin "6") (pinfunction "6_6") (pintype "passive"))
      (node (ref "CHIP3") (pin "6") (pinfunction "6_6") (pintype "passive"))
      (node (ref "CHIP4") (pin "6") (pinfunction "6_6") (pintype "passive"))
      (node (ref "CHIP5") (pin "6") (pinfunction "6_6") (pintype "passive"))
      (node (ref "CHIP6") (pin "6") (pinfunction "6_6") (pintype "passive"))
      (node (ref "CHIP7") (pin "6") (pinfunction "6_6") (pintype "passive"))
      (node (ref "DEBUG") (pin "1") (pinfunction "VCC_1") (pintype "bidirectional"))
      (node (ref "Q2") (pin "1") (pinfunction "1_1") (pintype "bidirectional"))
      (node (ref "Q3") (pin "1") (pinfunction "1_1") (pintype "bidirectional"))
      (node (ref "Q4") (pin "1") (pinfunction "1_1") (pintype "bidirectional"))
      (node (ref "Q5") (pin "1") (pinfunction "1_1") (pintype "bidirectional"))
      (node (ref "R17") (pin "2") (pinfunction "2_2") (pintype "passive"))
      (node (ref "R2") (pin "2") (pinfunction "2_2") (pintype "passive"))
      (node (ref "R20") (pin "2") (pinfunction "2_2") (pintype "passive"))
      (node (ref "R21") (pin "2") (pinfunction "2_2") (pintype "passive"))
      (node (ref "R22") (pin "2") (pinfunction "2_2") (pintype "passive"))
      (node (ref "R3") (pin "1") (pinfunction "1_1") (pintype "passive"))
      (node (ref "R4") (pin "2") (pinfunction "2_2") (pintype "passive"))
      (node (ref "R44") (pin "2") (pinfunction "2_2") (pintype "passive"))
      (node (ref "R45") (pin "2") (pinfunction "2_2") (pintype "passive"))
      (node (ref "R47") (pin "2") (pinfunction "2_2") (pintype "passive"))
      (node (ref "R49") (pin "1") (pinfunction "1_1") (pintype "passive"))
      (node (ref "R50") (pin "2") (pinfunction "2_2") (pintype "passive"))
      (node (ref "R55") (pin "2") (pinfunction "2_2") (pintype "passive"))
      (node (ref "R57") (pin "2") (pinfunction "2_2") (pintype "passive"))
      (node (ref "R59") (pin "2") (pinfunction "2_2") (pintype "passive"))
      (node (ref "R6") (pin "2") (pinfunction "2_2") (pintype "passive"))
      (node (ref "R60") (pin "2") (pinfunction "2_2") (pintype "passive"))
      (node (ref "R61") (pin "2") (pinfunction "2_2") (pintype "passive"))
      (node (ref "R62") (pin "2") (pinfunction "2_2") (pintype "passive"))
      (node (ref "R63") (pin "2") (pinfunction "2_2") (pintype "passive"))
      (node (ref "R64") (pin "2") (pinfunction "2_2") (pintype "passive"))
      (node (ref "R65") (pin "2") (pinfunction "2_2") (pintype "passive"))
      (node (ref "R66") (pin "2") (pinfunction "2_2") (pintype "passive"))
      (node (ref "R67") (pin "2") (pinfunction "2_2") (pintype "passive"))
      (node (ref "R68") (pin "2") (pinfunction "2_2") (pintype "passive"))
      (node (ref "R69") (pin "2") (pinfunction "2_2") (pintype "passive"))
      (node (ref "R7") (pin "2") (pinfunction "2_2") (pintype "passive"))
      (node (ref "R70") (pin "2") (pinfunction "2_2") (pintype "passive"))
      (node (ref "R71") (pin "2") (pinfunction "2_2") (pintype "passive"))
      (node (ref "R72") (pin "2") (pinfunction "2_2") (pintype "passive"))
      (node (ref "R78") (pin "2") (pinfunction "2_2") (pintype "passive"))
      (node (ref "R79") (pin "2") (pinfunction "2_2") (pintype "passive"))
      (node (ref "R8") (pin "2") (pinfunction "2_2") (pintype "passive"))
      (node (ref "R83") (pin "2") (pinfunction "2_2") (pintype "passive"))
      (node (ref "R9") (pin "2") (pinfunction "2_2") (pintype "passive"))
      (node (ref "SD1") (pin "4") (pinfunction "VDD_4") (pintype "power_in"))
      (node (ref "T1") (pin "3") (pinfunction "VDD_3") (pintype "bidirectional"))
      (node (ref "T2") (pin "3") (pinfunction "VDD_3") (pintype "bidirectional"))
      (node (ref "T3") (pin "3") (pinfunction "VDD_3") (pintype "bidirectional"))
      (node (ref "TP2") (pin "P$1") (pinfunction "P$1_P$1") (pintype "bidirectional"))
      (node (ref "U10") (pin "5") (pinfunction "V+_5") (pintype "bidirectional"))
      (node (ref "U2") (pin "2") (pinfunction "OUT_2") (pintype "passive"))
      (node (ref "U2") (pin "4") (pinfunction "OUT_4") (pintype "passive"))
      (node (ref "U6") (pin "17") (pinfunction "VDDIO1_17") (pintype "power_in"))
      (node (ref "U6") (pin "36") (pinfunction "VDDIO2_36") (pintype "power_in"))
      (node (ref "U6") (pin "44") (pinfunction "VDDIN_44") (pintype "power_in"))
      (node (ref "U6") (pin "6") (pinfunction "VDDANA_6") (pintype "power_in"))
      (node (ref "U7") (pin "5") (pinfunction "OUT_5") (pintype "power_in"))
      (node (ref "U9") (pin "5") (pinfunction "V+_5") (pintype "bidirectional"))
    )
    (net (code "2") (name "+5V") (class "Default")
      (node (ref "C10") (pin "1") (pinfunction "1_1") (pintype "passive"))
      (node (ref "C15") (pin "1") (pinfunction "1_1") (pintype "passive"))
      (node (ref "C17") (pin "1") (pinfunction "1_1") (pintype "passive"))
      (node (ref "C19") (pin "1") (pinfunction "1_1") (pintype "passive"))
      (node (ref "C2") (pin "1") (pinfunction "1_1") (pintype "passive"))
      (node (ref "C25") (pin "2") (pinfunction "2_2") (pintype "passive"))
      (node (ref "C26") (pin "1") (pinfunction "1_1") (pintype "passive"))
      (node (ref "C3") (pin "1") (pinfunction "1_1") (pintype "passive"))
      (node (ref "C35") (pin "1") (pinfunction "1_1") (pintype "passive"))
      (node (ref "C36") (pin "1") (pinfunction "1_1") (pintype "passive"))
      (node (ref "C44") (pin "1") (pinfunction "1_1") (pintype "passive"))
      (node (ref "C45") (pin "1") (pinfunction "1_1") (pintype "passive"))
      (node (ref "D1") (pin "A") (pinfunction "A_A") (pintype "passive"))
      (node (ref "L3") (pin "2") (pinfunction "2_2") (pintype "passive"))
      (node (ref "Q1") (pin "2") (pinfunction "S_2") (pintype "passive"))
      (node (ref "R1") (pin "1") (pinfunction "1_1") (pintype "passive"))
      (node (ref "R10") (pin "2") (pinfunction "2_2") (pintype "passive"))
      (node (ref "R15") (pin "2") (pinfunction "2_2") (pintype "passive"))
      (node (ref "R16") (pin "2") (pinfunction "2_2") (pintype "passive"))
      (node (ref "R19") (pin "2") (pinfunction "2_2") (pintype "passive"))
      (node (ref "R25") (pin "2") (pinfunction "2_2") (pintype "passive"))
      (node (ref "R37") (pin "1") (pinfunction "1_1") (pintype "passive"))
      (node (ref "TEC1") (pin "1") (pinfunction "1_1") (pintype "passive"))
      (node (ref "TEC2") (pin "1") (pinfunction "1_1") (pintype "passive"))
      (node (ref "TEC3") (pin "1") (pinfunction "1_1") (pintype "passive"))
      (node (ref "TEC4") (pin "1") (pinfunction "1_1") (pintype "passive"))
      (node (ref "TP3") (pin "P$1") (pinfunction "P$1_P$1") (pintype "bidirectional"))
      (node (ref "U1") (pin "10") (pinfunction "VIN_10") (pintype "bidirectional"))
      (node (ref "U1") (pin "11") (pinfunction "VIN_2_11") (pintype "bidirectional"))
      (node (ref "U1") (pin "13") (pinfunction "PS/SYNC_13") (pintype "bidirectional"))
      (node (ref "U11") (pin "10") (pinfunction "VIN_10") (pintype "bidirectional"))
      (node (ref "U11") (pin "11") (pinfunction "VIN_2_11") (pintype "bidirectional"))
      (node (ref "U11") (pin "13") (pinfunction "PS/SYNC_13") (pintype "bidirectional"))
      (node (ref "U4") (pin "1") (pinfunction "VDD_1") (pintype "power_in"))
      (node (ref "U5") (pin "10") (pinfunction "VIN_10") (pintype "bidirectional"))
      (node (ref "U5") (pin "11") (pinfunction "VIN_2_11") (pintype "bidirectional"))
      (node (ref "U5") (pin "13") (pinfunction "PS/SYNC_13") (pintype "bidirectional"))
      (node (ref "U8") (pin "10") (pinfunction "VIN_10") (pintype "bidirectional"))
      (node (ref "U8") (pin "11") (pinfunction "VIN_2_11") (pintype "bidirectional"))
      (node (ref "U8") (pin "13") (pinfunction "PS/SYNC_13") (pintype "bidirectional"))
    )
    (net (code "3") (name "+12V") (class "Default")
      (node (ref "C11") (pin "1") (pinfunction "1_1") (pintype "passive"))
      (node (ref "C14") (pin "1") (pinfunction "1_1") (pintype "passive"))
      (node (ref "C22") (pin "1") (pinfunction "1_1") (pintype "passive"))
      (node (ref "C23") (pin "2") (pinfunction "2_2") (pintype "passive"))
      (node (ref "C30") (pin "1") (pinfunction "1_1") (pintype "passive"))
      (node (ref "J2") (pin "1") (pinfunction "1_1") (pintype "passive"))
      (node (ref "R30") (pin "2") (pinfunction "2_2") (pintype "passive"))
      (node (ref "R33") (pin "1") (pinfunction "1_1") (pintype "passive"))
      (node (ref "R34") (pin "1") (pinfunction "1_1") (pintype "passive"))
      (node (ref "SJ1") (pin "1") (pinfunction "1_1") (pintype "passive"))
      (node (ref "TP4") (pin "P$1") (pinfunction "P$1_P$1") (pintype "bidirectional"))
      (node (ref "U3") (pin "8") (pinfunction "VIN_8") (pintype "bidirectional"))
    )
    (net (code "4") (name "1W_TEMP") (class "Default")
      (node (ref "R78") (pin "1") (pinfunction "1_1") (pintype "passive"))
      (node (ref "T1") (pin "2") (pinfunction "DQ_2") (pintype "bidirectional"))
      (node (ref "T2") (pin "2") (pinfunction "DQ_2") (pintype "bidirectional"))
      (node (ref "T3") (pin "2") (pinfunction "DQ_2") (pintype "bidirectional"))
      (node (ref "U6") (pin "30") (pinfunction "PA21/I5/SERCOM3+5.3/I2SFS0_30") (pintype "bidirectional"))
    )
    (net (code "5") (name "BTN_1") (class "Default")
      (node (ref "R2") (pin "1") (pinfunction "1_1") (pintype "passive"))
      (node (ref "SW1") (pin "A") (pinfunction "P_A") (pintype "passive"))
      (node (ref "SW1") (pin "A'") (pinfunction "P1_A'") (pintype "passive"))
      (node (ref "U6") (pin "47") (pinfunction "PB02/I2/AIN10/SERCOM5.0_47") (pintype "bidirectional"))
    )
    (net (code "6") (name "BTN_2") (class "Default")
      (node (ref "R9") (pin "1") (pinfunction "1_1") (pintype "passive"))
      (node (ref "SW2") (pin "A") (pinfunction "P_A") (pintype "passive"))
      (node (ref "SW2") (pin "A'") (pinfunction "P1_A'") (pintype "passive"))
      (node (ref "U6") (pin "48") (pinfunction "PB03/I3/AIN11/SERCOM5.1_48") (pintype "bidirectional"))
    )
    (net (code "7") (name "CARD_DETECT") (class "Default")
      (node (ref "R83") (pin "1") (pinfunction "1_1") (pintype "passive"))
      (node (ref "SD1") (pin "CD1") (pinfunction "CARD_DETECT_CD1") (pintype "passive"))
      (node (ref "U6") (pin "37") (pinfunction "PB22/I6/SERCOM5.2_37") (pintype "bidirectional"))
    )
    (net (code "8") (name "CHIP0_RES") (class "Default")
      (node (ref "CHIP0") (pin "3") (pinfunction "3_3") (pintype "passive"))
      (node (ref "R60") (pin "1") (pinfunction "1_1") (pintype "passive"))
      (node (ref "U10") (pin "15") (pinfunction "IN1_15") (pintype "bidirectional"))
    )
    (net (code "9") (name "CHIP0_STATUS") (class "Default")
      (node (ref "CHIP0") (pin "2") (pinfunction "2_2") (pintype "passive"))
      (node (ref "U6") (pin "24") (pinfunction "PA15/I15/SERCOM3+4.3_24") (pintype "bidirectional"))
    )
    (net (code "10") (name "CHIP0_TH") (class "Default")
      (node (ref "CHIP0") (pin "4") (pinfunction "4_4") (pintype "passive"))
      (node (ref "R57") (pin "1") (pinfunction "1_1") (pintype "passive"))
      (node (ref "U10") (pin "16") (pinfunction "IN0_16") (pintype "bidirectional"))
    )
    (net (code "11") (name "CHIP1_RES") (class "Default")
      (node (ref "CHIP1") (pin "3") (pinfunction "3_3") (pintype "passive"))
      (node (ref "R64") (pin "1") (pinfunction "1_1") (pintype "passive"))
      (node (ref "U10") (pin "13") (pinfunction "IN3_13") (pintype "bidirectional"))
    )
    (net (code "12") (name "CHIP1_STATUS") (class "Default")
      (node (ref "CHIP1") (pin "2") (pinfunction "2_2") (pintype "passive"))
      (node (ref "U6") (pin "23") (pinfunction "PA14/I14/SERCOM2+4.2_23") (pintype "bidirectional"))
    )
    (net (code "13") (name "CHIP1_TH") (class "Default")
      (node (ref "CHIP1") (pin "4") (pinfunction "4_4") (pintype "passive"))
      (node (ref "R62") (pin "1") (pinfunction "1_1") (pintype "passive"))
      (node (ref "U10") (pin "14") (pinfunction "IN2_14") (pintype "bidirectional"))
    )
    (net (code "14") (name "CHIP2_RES") (class "Default")
      (node (ref "CHIP2") (pin "3") (pinfunction "3_3") (pintype "passive"))
      (node (ref "R68") (pin "1") (pinfunction "1_1") (pintype "passive"))
      (node (ref "U10") (pin "11") (pinfunction "IN5_11") (pintype "bidirectional"))
    )
    (net (code "15") (name "CHIP2_STATUS") (class "Default")
      (node (ref "CHIP2") (pin "2") (pinfunction "2_2") (pintype "passive"))
      (node (ref "U6") (pin "16") (pinfunction "PA11/I11/AIN19/SERCOM0+2.3/I2SF0_16") (pintype "bidirectional"))
    )
    (net (code "16") (name "CHIP2_TH") (class "Default")
      (node (ref "CHIP2") (pin "4") (pinfunction "4_4") (pintype "passive"))
      (node (ref "R66") (pin "1") (pinfunction "1_1") (pintype "passive"))
      (node (ref "U10") (pin "12") (pinfunction "IN4_12") (pintype "bidirectional"))
    )
    (net (code "17") (name "CHIP3_RES") (class "Default")
      (node (ref "CHIP3") (pin "3") (pinfunction "3_3") (pintype "passive"))
      (node (ref "R72") (pin "1") (pinfunction "1_1") (pintype "passive"))
      (node (ref "U10") (pin "9") (pinfunction "IN7_9") (pintype "bidirectional"))
    )
    (net (code "18") (name "CHIP3_STATUS") (class "Default")
      (node (ref "CHIP3") (pin "2") (pinfunction "2_2") (pintype "passive"))
      (node (ref "U6") (pin "15") (pinfunction "PA10/I10/AIN18/SERCOM0+2.2/I2SCK_15") (pintype "bidirectional"))
    )
    (net (code "19") (name "CHIP3_TH") (class "Default")
      (node (ref "CHIP3") (pin "4") (pinfunction "4_4") (pintype "passive"))
      (node (ref "R70") (pin "1") (pinfunction "1_1") (pintype "passive"))
      (node (ref "U10") (pin "10") (pinfunction "IN6_10") (pintype "bidirectional"))
    )
    (net (code "20") (name "CHIP4_RES") (class "Default")
      (node (ref "CHIP4") (pin "3") (pinfunction "3_3") (pintype "passive"))
      (node (ref "R59") (pin "1") (pinfunction "1_1") (pintype "passive"))
      (node (ref "U9") (pin "15") (pinfunction "IN1_15") (pintype "bidirectional"))
    )
    (net (code "21") (name "CHIP4_STATUS") (class "Default")
      (node (ref "CHIP4") (pin "2") (pinfunction "2_2") (pintype "passive"))
      (node (ref "U6") (pin "12") (pinfunction "PA07/I7/AIN7/SERCOM0.3/I2SD0_12") (pintype "bidirectional"))
    )
    (net (code "22") (name "CHIP4_TH") (class "Default")
      (node (ref "CHIP4") (pin "4") (pinfunction "4_4") (pintype "passive"))
      (node (ref "R55") (pin "1") (pinfunction "1_1") (pintype "passive"))
      (node (ref "U9") (pin "16") (pinfunction "IN0_16") (pintype "bidirectional"))
    )
    (net (code "23") (name "CHIP5_RES") (class "Default")
      (node (ref "CHIP5") (pin "3") (pinfunction "3_3") (pintype "passive"))
      (node (ref "R63") (pin "1") (pinfunction "1_1") (pintype "passive"))
      (node (ref "U9") (pin "13") (pinfunction "IN3_13") (pintype "bidirectional"))
    )
    (net (code "24") (name "CHIP5_STATUS") (class "Default")
      (node (ref "CHIP5") (pin "2") (pinfunction "2_2") (pintype "passive"))
      (node (ref "U6") (pin "11") (pinfunction "PA06/EINT6/AIN6/SERCOM0.2_11") (pintype "bidirectional"))
    )
    (net (code "25") (name "CHIP5_TH") (class "Default")
      (node (ref "CHIP5") (pin "4") (pinfunction "4_4") (pintype "passive"))
      (node (ref "R61") (pin "1") (pinfunction "1_1") (pintype "passive"))
      (node (ref "U9") (pin "14") (pinfunction "IN2_14") (pintype "bidirectional"))
    )
    (net (code "26") (name "CHIP6_RES") (class "Default")
      (node (ref "CHIP6") (pin "3") (pinfunction "3_3") (pintype "passive"))
      (node (ref "R67") (pin "1") (pinfunction "1_1") (pintype "passive"))
      (node (ref "U9") (pin "11") (pinfunction "IN5_11") (pintype "bidirectional"))
    )
    (net (code "27") (name "CHIP6_STATUS") (class "Default")
      (node (ref "CHIP6") (pin "2") (pinfunction "2_2") (pintype "passive"))
      (node (ref "U6") (pin "38") (pinfunction "PB23/I7/SERCOM5.3_38") (pintype "bidirectional"))
    )
    (net (code "28") (name "CHIP6_TH") (class "Default")
      (node (ref "CHIP6") (pin "4") (pinfunction "4_4") (pintype "passive"))
      (node (ref "R65") (pin "1") (pinfunction "1_1") (pintype "passive"))
      (node (ref "U9") (pin "12") (pinfunction "IN4_12") (pintype "bidirectional"))
    )
    (net (code "29") (name "CHIP7_RES") (class "Default")
      (node (ref "CHIP7") (pin "3") (pinfunction "3_3") (pintype "passive"))
      (node (ref "R71") (pin "1") (pinfunction "1_1") (pintype "passive"))
      (node (ref "U9") (pin "9") (pinfunction "IN7_9") (pintype "bidirectional"))
    )
    (net (code "30") (name "CHIP7_STATUS") (class "Default")
      (node (ref "CHIP7") (pin "2") (pinfunction "2_2") (pintype "passive"))
      (node (ref "U6") (pin "39") (pinfunction "PA27/I15_39") (pintype "bidirectional"))
    )
    (net (code "31") (name "CHIP7_TH") (class "Default")
      (node (ref "CHIP7") (pin "4") (pinfunction "4_4") (pintype "passive"))
      (node (ref "R69") (pin "1") (pinfunction "1_1") (pintype "passive"))
      (node (ref "U9") (pin "10") (pinfunction "IN6_10") (pintype "bidirectional"))
    )
    (net (code "32") (name "DAC") (class "Default")
      (node (ref "TP1") (pin "TP") (pinfunction "TP_TP") (pintype "input"))
      (node (ref "U6") (pin "3") (pinfunction "PA02/EINT2/AIN0/Y0/VOUT1_3") (pintype "bidirectional"))
    )
    (net (code "33") (name "EN") (class "Default")
      (node (ref "Q1") (pin "3") (pinfunction "D_3") (pintype "passive"))
      (node (ref "R5") (pin "2") (pinfunction "2_2") (pintype "passive"))
      (node (ref "U1") (pin "12") (pinfunction "EN_12") (pintype "bidirectional"))
      (node (ref "U11") (pin "12") (pinfunction "EN_12") (pintype "bidirectional"))
      (node (ref "U5") (pin "12") (pinfunction "EN_12") (pintype "bidirectional"))
      (node (ref "U8") (pin "12") (pinfunction "EN_12") (pintype "bidirectional"))
    )
    (net (code "34") (name "GND") (class "Default")
      (node (ref "C1") (pin "2") (pinfunction "2_2") (pintype "passive"))
      (node (ref "C10") (pin "2") (pinfunction "2_2") (pintype "passive"))
      (node (ref "C15") (pin "2") (pinfunction "2_2") (pintype "passive"))
      (node (ref "C18") (pin "2") (pinfunction "2_2") (pintype "passive"))
      (node (ref "C20") (pin "2") (pinfunction "2_2") (pintype "passive"))
      (node (ref "C21") (pin "2") (pinfunction "2_2") (pintype "passive"))
      (node (ref "C27") (pin "2") (pinfunction "2_2") (pintype "passive"))
      (node (ref "C29") (pin "2") (pinfunction "2_2") (pintype "passive"))
      (node (ref "C32") (pin "2") (pinfunction "2_2") (pintype "passive"))
      (node (ref "C33") (pin "2") (pinfunction "2_2") (pintype "passive"))
      (node (ref "C34") (pin "2") (pinfunction "2_2") (pintype "passive"))
      (node (ref "C37") (pin "2") (pinfunction "2_2") (pintype "passive"))
      (node (ref "C38") (pin "2") (pinfunction "2_2") (pintype "passive"))
      (node (ref "C39") (pin "2") (pinfunction "2_2") (pintype "passive"))
      (node (ref "C4") (pin "2") (pinfunction "2_2") (pintype "passive"))
      (node (ref "C40") (pin "2") (pinfunction "2_2") (pintype "passive"))
      (node (ref "C41") (pin "2") (pinfunction "2_2") (pintype "passive"))
      (node (ref "C46") (pin "2") (pinfunction "2_2") (pintype "passive"))
      (node (ref "C49") (pin "2") (pinfunction "2_2") (pintype "passive"))
      (node (ref "C6") (pin "2") (pinfunction "2_2") (pintype "passive"))
      (node (ref "C7") (pin "2") (pinfunction "2_2") (pintype "passive"))
      (node (ref "C8") (pin "2") (pinfunction "2_2") (pintype "passive"))
      (node (ref "CHIP0") (pin "1") (pinfunction "1_1") (pintype "passive"))
      (node (ref "CHIP1") (pin "1") (pinfunction "1_1") (pintype "passive"))
      (node (ref "CHIP2") (pin "1") (pinfunction "1_1") (pintype "passive"))
      (node (ref "CHIP3") (pin "1") (pinfunction "1_1") (pintype "passive"))
      (node (ref "CHIP4") (pin "1") (pinfunction "1_1") (pintype "passive"))
      (node (ref "CHIP5") (pin "1") (pinfunction "1_1") (pintype "passive"))
      (node (ref "CHIP6") (pin "1") (pinfunction "1_1") (pintype "passive"))
      (node (ref "CHIP7") (pin "1") (pinfunction "1_1") (pintype "passive"))
      (node (ref "DEBUG") (pin "3") (pinfunction "GND_3") (pintype "bidirectional"))
      (node (ref "DEBUG") (pin "5") (pinfunction "GND_5") (pintype "bidirectional"))
      (node (ref "JP1") (pin "4") (pinfunction "4_4") (pintype "passive"))
      (node (ref "LED1") (pin "C") (pinfunction "C_C") (pintype "passive"))
      (node (ref "R24") (pin "1") (pinfunction "1_1") (pintype "passive"))
      (node (ref "R27") (pin "2") (pinfunction "2_2") (pintype "passive"))
      (node (ref "R31") (pin "2") (pinfunction "2_2") (pintype "passive"))
      (node (ref "R36") (pin "2") (pinfunction "2_2") (pintype "passive"))
      (node (ref "R40") (pin "1") (pinfunction "1_1") (pintype "passive"))
      (node (ref "R46") (pin "1") (pinfunction "1_1") (pintype "passive"))
      (node (ref "R48") (pin "1") (pinfunction "1_1") (pintype "passive"))
      (node (ref "R5") (pin "1") (pinfunction "1_1") (pintype "passive"))
      (node (ref "R51") (pin "1") (pinfunction "1_1") (pintype "passive"))
      (node (ref "R53") (pin "1") (pinfunction "1_1") (pintype "passive"))
      (node (ref "R74") (pin "1") (pinfunction "1_1") (pintype "passive"))
      (node (ref "RESET") (pin "B") (pinfunction "S_B") (pintype "passive"))
      (node (ref "RESET") (pin "B'") (pinfunction "S1_B'") (pintype "passive"))
      (node (ref "SD1") (pin "6") (pinfunction "VSS_6") (pintype "power_in"))
      (node (ref "SD1") (pin "MT1") (pinfunction "GND_MT1") (pintype "power_in"))
      (node (ref "SD1") (pin "MT2") (pinfunction "GND1_MT2") (pintype "power_in"))
      (node (ref "SW1") (pin "B") (pinfunction "S_B") (pintype "passive"))
      (node (ref "SW1") (pin "B'") (pinfunction "S1_B'") (pintype "passive"))
      (node (ref "SW2") (pin "B") (pinfunction "S_B") (pintype "passive"))
      (node (ref "SW2") (pin "B'") (pinfunction "S1_B'") (pintype "passive"))
      (node (ref "T1") (pin "1") (pinfunction "GND_1") (pintype "bidirectional"))
      (node (ref "T2") (pin "1") (pinfunction "GND_1") (pintype "bidirectional"))
      (node (ref "T3") (pin "1") (pinfunction "GND_1") (pintype "bidirectional"))
      (node (ref "TP5") (pin "P$1") (pinfunction "P$1_P$1") (pintype "bidirectional"))
      (node (ref "U1") (pin "2") (pinfunction "GND_2") (pintype "bidirectional"))
      (node (ref "U10") (pin "4") (pinfunction "GND_4") (pintype "bidirectional"))
      (node (ref "U11") (pin "2") (pinfunction "GND_2") (pintype "bidirectional"))
      (node (ref "U4") (pin "10") (pinfunction "VSS_10") (pintype "power_in"))
      (node (ref "U5") (pin "2") (pinfunction "GND_2") (pintype "bidirectional"))
      (node (ref "U6") (pin "18") (pinfunction "GND1_18") (pintype "power_in"))
      (node (ref "U6") (pin "35") (pinfunction "GND2_35") (pintype "power_in"))
      (node (ref "U6") (pin "42") (pinfunction "GND3_42") (pintype "power_in"))
      (node (ref "U6") (pin "5") (pinfunction "GNDANA_5") (pintype "power_in"))
      (node (ref "U8") (pin "2") (pinfunction "GND_2") (pintype "bidirectional"))
      (node (ref "U9") (pin "4") (pinfunction "GND_4") (pintype "bidirectional"))
      (node (ref "USB") (pin "BASE@1") (pinfunction "GND_BASE@1") (pintype "power_in"))
      (node (ref "USB") (pin "BASE@2") (pinfunction "GND_BASE@2") (pintype "power_in"))
      (node (ref "USB") (pin "GND") (pinfunction "GND_GND") (pintype "power_in"))
      (node (ref "USB") (pin "SPRT@1") (pinfunction "GND_SPRT@1") (pintype "power_in"))
      (node (ref "USB") (pin "SPRT@2") (pinfunction "GND_SPRT@2") (pintype "power_in"))
      (node (ref "USB") (pin "SPRT@3") (pinfunction "GND_SPRT@3") (pintype "power_in"))
      (node (ref "USB") (pin "SPRT@4") (pinfunction "GND_SPRT@4") (pintype "power_in"))
    )
    (net (code "35") (name "GNDA") (class "Default")
      (node (ref "C11") (pin "2") (pinfunction "2_2") (pintype "passive"))
      (node (ref "C12") (pin "2") (pinfunction "2_2") (pintype "passive"))
      (node (ref "C13") (pin "2") (pinfunction "2_2") (pintype "passive"))
      (node (ref "C14") (pin "2") (pinfunction "2_2") (pintype "passive"))
      (node (ref "C16") (pin "2") (pinfunction "2_2") (pintype "passive"))
      (node (ref "C17") (pin "2") (pinfunction "2_2") (pintype "passive"))
      (node (ref "C19") (pin "2") (pinfunction "2_2") (pintype "passive"))
      (node (ref "C2") (pin "2") (pinfunction "2_2") (pintype "passive"))
      (node (ref "C26") (pin "2") (pinfunction "2_2") (pintype "passive"))
      (node (ref "C28") (pin "2") (pinfunction "2_2") (pintype "passive"))
      (node (ref "C3") (pin "2") (pinfunction "2_2") (pintype "passive"))
      (node (ref "C30") (pin "2") (pinfunction "2_2") (pintype "passive"))
      (node (ref "C31") (pin "2") (pinfunction "2_2") (pintype "passive"))
      (node (ref "C35") (pin "2") (pinfunction "2_2") (pintype "passive"))
      (node (ref "C36") (pin "2") (pinfunction "2_2") (pintype "passive"))
      (node (ref "C42") (pin "2") (pinfunction "2_2") (pintype "passive"))
      (node (ref "C43") (pin "2") (pinfunction "2_2") (pintype "passive"))
      (node (ref "C44") (pin "2") (pinfunction "2_2") (pintype "passive"))
      (node (ref "C45") (pin "2") (pinfunction "2_2") (pintype "passive"))
      (node (ref "C47") (pin "2") (pinfunction "2_2") (pintype "passive"))
      (node (ref "C48") (pin "2") (pinfunction "2_2") (pintype "passive"))
      (node (ref "C50") (pin "2") (pinfunction "2_2") (pintype "passive"))
      (node (ref "C51") (pin "-") (pinfunction "-_-") (pintype "passive"))
      (node (ref "C9") (pin "2") (pinfunction "2_2") (pintype "passive"))
      (node (ref "D2") (pin "1") (pinfunction "A_1") (pintype "passive"))
      (node (ref "J2") (pin "2") (pinfunction "2_2") (pintype "passive"))
      (node (ref "J2") (pin "3") (pinfunction "3_3") (pintype "passive"))
      (node (ref "R27") (pin "1") (pinfunction "1_1") (pintype "passive"))
      (node (ref "R31") (pin "1") (pinfunction "1_1") (pintype "passive"))
      (node (ref "R36") (pin "1") (pinfunction "1_1") (pintype "passive"))
      (node (ref "R38") (pin "2") (pinfunction "2_2") (pintype "passive"))
      (node (ref "R82") (pin "2") (pinfunction "2_2") (pintype "passive"))
      (node (ref "TP6") (pin "P$1") (pinfunction "P$1_P$1") (pintype "bidirectional"))
      (node (ref "U1") (pin "15") (pinfunction "PGND_15") (pintype "bidirectional"))
      (node (ref "U1") (pin "16") (pinfunction "PGND1_16") (pintype "bidirectional"))
      (node (ref "U1") (pin "17") (pinfunction "PGND2_17") (pintype "bidirectional"))
      (node (ref "U1") (pin "18") (pinfunction "PGND3_18") (pintype "bidirectional"))
      (node (ref "U1") (pin "19") (pinfunction "PGND4_19") (pintype "bidirectional"))
      (node (ref "U1") (pin "20") (pinfunction "PGND5_20") (pintype "bidirectional"))
      (node (ref "U1") (pin "21") (pinfunction "PGND6_21") (pintype "bidirectional"))
      (node (ref "U1") (pin "22") (pinfunction "PGND7_22") (pintype "bidirectional"))
      (node (ref "U1") (pin "23") (pinfunction "PGND8_23") (pintype "bidirectional"))
      (node (ref "U11") (pin "15") (pinfunction "PGND_15") (pintype "bidirectional"))
      (node (ref "U11") (pin "16") (pinfunction "PGND1_16") (pintype "bidirectional"))
      (node (ref "U11") (pin "17") (pinfunction "PGND2_17") (pintype "bidirectional"))
      (node (ref "U11") (pin "18") (pinfunction "PGND3_18") (pintype "bidirectional"))
      (node (ref "U11") (pin "19") (pinfunction "PGND4_19") (pintype "bidirectional"))
      (node (ref "U11") (pin "20") (pinfunction "PGND5_20") (pintype "bidirectional"))
      (node (ref "U11") (pin "21") (pinfunction "PGND6_21") (pintype "bidirectional"))
      (node (ref "U11") (pin "22") (pinfunction "PGND7_22") (pintype "bidirectional"))
      (node (ref "U11") (pin "23") (pinfunction "PGND8_23") (pintype "bidirectional"))
      (node (ref "U12") (pin "1") (pinfunction "GND_1") (pintype "power_in"))
      (node (ref "U12") (pin "7") (pinfunction "PGND_7") (pintype "power_in"))
      (node (ref "U12") (pin "GND") (pinfunction "GND_GND") (pintype "power_in"))
      (node (ref "U12") (pin "P$1") (pinfunction "GND_P$1") (pintype "power_in"))
      (node (ref "U12") (pin "P$2") (pinfunction "GND_P$2") (pintype "power_in"))
      (node (ref "U12") (pin "P$3") (pinfunction "GND_P$3") (pintype "power_in"))
      (node (ref "U12") (pin "P$4") (pinfunction "GND_P$4") (pintype "power_in"))
      (node (ref "U2") (pin "1") (pinfunction "GND/ADJ_1") (pintype "input"))
      (node (ref "U3") (pin "4") (pinfunction "GND_4") (pintype "bidirectional"))
      (node (ref "U3") (pin "9") (pinfunction "GND_9") (pintype "bidirectional"))
      (node (ref "U5") (pin "15") (pinfunction "PGND_15") (pintype "bidirectional"))
      (node (ref "U5") (pin "16") (pinfunction "PGND1_16") (pintype "bidirectional"))
      (node (ref "U5") (pin "17") (pinfunction "PGND2_17") (pintype "bidirectional"))
      (node (ref "U5") (pin "18") (pinfunction "PGND3_18") (pintype "bidirectional"))
      (node (ref "U5") (pin "19") (pinfunction "PGND4_19") (pintype "bidirectional"))
      (node (ref "U5") (pin "20") (pinfunction "PGND5_20") (pintype "bidirectional"))
      (node (ref "U5") (pin "21") (pinfunction "PGND6_21") (pintype "bidirectional"))
      (node (ref "U5") (pin "22") (pinfunction "PGND7_22") (pintype "bidirectional"))
      (node (ref "U5") (pin "23") (pinfunction "PGND8_23") (pintype "bidirectional"))
      (node (ref "U7") (pin "2") (pinfunction "GND_2") (pintype "power_in"))
      (node (ref "U8") (pin "15") (pinfunction "PGND_15") (pintype "bidirectional"))
      (node (ref "U8") (pin "16") (pinfunction "PGND1_16") (pintype "bidirectional"))
      (node (ref "U8") (pin "17") (pinfunction "PGND2_17") (pintype "bidirectional"))
      (node (ref "U8") (pin "18") (pinfunction "PGND3_18") (pintype "bidirectional"))
      (node (ref "U8") (pin "19") (pinfunction "PGND4_19") (pintype "bidirectional"))
      (node (ref "U8") (pin "20") (pinfunction "PGND5_20") (pintype "bidirectional"))
      (node (ref "U8") (pin "21") (pinfunction "PGND6_21") (pintype "bidirectional"))
      (node (ref "U8") (pin "22") (pinfunction "PGND7_22") (pintype "bidirectional"))
      (node (ref "U8") (pin "23") (pinfunction "PGND8_23") (pintype "bidirectional"))
    )
    (net (code "36") (name "LDAC") (class "Default")
      (node (ref "U4") (pin "4") (pinfunction "*LDAC_4") (pintype "input"))
      (node (ref "U6") (pin "9") (pinfunction "PA04/EINT4/VREFB/AIN4/SERCOM0.0_9") (pintype "bidirectional"))
    )
    (net (code "37") (name "MISO") (class "Default")
      (node (ref "SD1") (pin "7") (pinfunction "DATA_OUT_7") (pintype "output"))
      (node (ref "TP14") (pin "P$1") (pinfunction "P$1_P$1") (pintype "bidirectional"))
      (node (ref "U6") (pin "28") (pinfunction "PA19/I3/SERCOM1+3.3/I2SD0_28") (pintype "bidirectional"))
    )
    (net (code "38") (name "MOSI") (class "Default")
      (node (ref "SD1") (pin "3") (pinfunction "DATA_IN_3") (pintype "input"))
      (node (ref "TP13") (pin "P$1") (pinfunction "P$1_P$1") (pintype "bidirectional"))
      (node (ref "U6") (pin "25") (pinfunction "PA16/I2C/I0/SERCOM1+3.0_25") (pintype "bidirectional"))
    )
    (net (code "39") (name "Net-(C1-Pad1)") (class "Default")
      (node (ref "C1") (pin "1") (pinfunction "1_1") (pintype "passive"))
      (node (ref "JP1") (pin "3") (pinfunction "3_3") (pintype "passive"))
      (node (ref "R1") (pin "2") (pinfunction "2_2") (pintype "passive"))
      (node (ref "R3") (pin "2") (pinfunction "2_2") (pintype "passive"))
    )
    (net (code "40") (name "Net-(C24-Pad1)") (class "Default")
      (node (ref "C24") (pin "1") (pinfunction "1_1") (pintype "passive"))
      (node (ref "C25") (pin "1") (pinfunction "1_1") (pintype "passive"))
      (node (ref "R32") (pin "1") (pinfunction "1_1") (pintype "passive"))
    )
    (net (code "41") (name "Net-(D2-C)") (class "Default")
      (node (ref "D2") (pin "2") (pinfunction "C_2") (pintype "passive"))
      (node (ref "L3") (pin "1") (pinfunction "1_1") (pintype "passive"))
      (node (ref "Q6") (pin "5") (pinfunction "D_5") (pintype "passive"))
      (node (ref "Q6") (pin "6") (pinfunction "D_6") (pintype "passive"))
      (node (ref "Q6") (pin "7") (pinfunction "D_7") (pintype "passive"))
      (node (ref "Q6") (pin "8") (pinfunction "D_8") (pintype "passive"))
      (node (ref "Q6") (pin "9") (pinfunction "D_9") (pintype "passive"))
      (node (ref "R32") (pin "2") (pinfunction "2_2") (pintype "passive"))
    )
    (net (code "42") (name "Net-(JP1-Pad1)") (class "Default")
      (node (ref "JP1") (pin "1") (pinfunction "1_1") (pintype "passive"))
      (node (ref "R11") (pin "1") (pinfunction "1_1") (pintype "passive"))
      (node (ref "R12") (pin "1") (pinfunction "1_1") (pintype "passive"))
    )
    (net (code "43") (name "Net-(JP1-Pad2)") (class "Default")
      (node (ref "JP1") (pin "2") (pinfunction "2_2") (pintype "passive"))
      (node (ref "R13") (pin "1") (pinfunction "1_1") (pintype "passive"))
      (node (ref "R14") (pin "1") (pinfunction "1_1") (pintype "passive"))
    )
    (net (code "44") (name "Net-(LED1-PadA)") (class "Default")
      (node (ref "LED1") (pin "A") (pinfunction "A_A") (pintype "passive"))
      (node (ref "R20") (pin "1") (pinfunction "1_1") (pintype "passive"))
    )
    (net (code "45") (name "Net-(Q6-G)") (class "Default")
      (node (ref "Q6") (pin "4") (pinfunction "G_4") (pintype "passive"))
      (node (ref "U3") (pin "6") (pinfunction "PGATE_6") (pintype "bidirectional"))
    )
    (net (code "46") (name "Net-(R26-Pad1)") (class "Default")
      (node (ref "R26") (pin "1") (pinfunction "1_1") (pintype "passive"))
      (node (ref "R28") (pin "2") (pinfunction "2_2") (pintype "passive"))
      (node (ref "R29") (pin "2") (pinfunction "2_2") (pintype "passive"))
    )
    (net (code "47") (name "Net-(R41-Pad1)") (class "Default")
      (node (ref "R41") (pin "1") (pinfunction "1_1") (pintype "passive"))
      (node (ref "R42") (pin "2") (pinfunction "2_2") (pintype "passive"))
      (node (ref "R43") (pin "2") (pinfunction "2_2") (pintype "passive"))
    )
    (net (code "48") (name "Net-(R54-Pad1)") (class "Default")
      (node (ref "R54") (pin "1") (pinfunction "1_1") (pintype "passive"))
      (node (ref "R56") (pin "2") (pinfunction "2_2") (pintype "passive"))
      (node (ref "R58") (pin "2") (pinfunction "2_2") (pintype "passive"))
    )
    (net (code "49") (name "Net-(R75-Pad1)") (class "Default")
      (node (ref "R75") (pin "1") (pinfunction "1_1") (pintype "passive"))
      (node (ref "R76") (pin "2") (pinfunction "2_2") (pintype "passive"))
      (node (ref "R77") (pin "2") (pinfunction "2_2") (pintype "passive"))
    )
    (net (code "50") (name "Net-(RESET-P)") (class "Default")
      (node (ref "R18") (pin "1") (pinfunction "1_1") (pintype "passive"))
      (node (ref "RESET") (pin "A") (pinfunction "P_A") (pintype "passive"))
      (node (ref "RESET") (pin "A'") (pinfunction "P1_A'") (pintype "passive"))
    )
    (net (code "51") (name "Net-(U1-FB)") (class "Default")
      (node (ref "R23") (pin "1") (pinfunction "1_1") (pintype "passive"))
      (node (ref "R24") (pin "2") (pinfunction "2_2") (pintype "passive"))
      (node (ref "R26") (pin "2") (pinfunction "2_2") (pintype "passive"))
      (node (ref "U1") (pin "3") (pinfunction "FB_3") (pintype "bidirectional"))
    )
    (net (code "52") (name "Net-(U1-L1)") (class "Default")
      (node (ref "L1") (pin "1") (pinfunction "1_1") (pintype "passive"))
      (node (ref "U1") (pin "8") (pinfunction "L1_8") (pintype "bidirectional"))
      (node (ref "U1") (pin "9") (pinfunction "L1_2_9") (pintype "bidirectional"))
    )
    (net (code "53") (name "Net-(U1-L2)") (class "Default")
      (node (ref "L1") (pin "2") (pinfunction "2_2") (pintype "passive"))
      (node (ref "U1") (pin "6") (pinfunction "L2_6") (pintype "bidirectional"))
      (node (ref "U1") (pin "7") (pinfunction "L2_2_7") (pintype "bidirectional"))
    )
    (net (code "54") (name "Net-(U1-VINA)") (class "Default")
      (node (ref "C4") (pin "1") (pinfunction "1_1") (pintype "passive"))
      (node (ref "U1") (pin "1") (pinfunction "VINA_1") (pintype "bidirectional"))
    )
    (net (code "55") (name "Net-(U1-VOUT)") (class "Default")
      (node (ref "C12") (pin "1") (pinfunction "1_1") (pintype "passive"))
      (node (ref "C16") (pin "1") (pinfunction "1_1") (pintype "passive"))
      (node (ref "R23") (pin "2") (pinfunction "2_2") (pintype "passive"))
      (node (ref "TEC4") (pin "2") (pinfunction "2_2") (pintype "passive"))
      (node (ref "U1") (pin "4") (pinfunction "VOUT_4") (pintype "bidirectional"))
      (node (ref "U1") (pin "5") (pinfunction "VOUT_2_5") (pintype "bidirectional"))
    )
    (net (code "56") (name "Net-(U3-ADJ)") (class "Default")
      (node (ref "C23") (pin "1") (pinfunction "1_1") (pintype "passive"))
      (node (ref "R33") (pin "2") (pinfunction "2_2") (pintype "passive"))
      (node (ref "U3") (pin "1") (pinfunction "ADJ_1") (pintype "bidirectional"))
    )
    (net (code "57") (name "Net-(U3-FB)") (class "Default")
      (node (ref "C24") (pin "2") (pinfunction "2_2") (pintype "passive"))
      (node (ref "R37") (pin "2") (pinfunction "2_2") (pintype "passive"))
      (node (ref "R38") (pin "1") (pinfunction "1_1") (pintype "passive"))
      (node (ref "U3") (pin "3") (pinfunction "FB_3") (pintype "bidirectional"))
    )
    (net (code "58") (name "Net-(U3-ISEN)") (class "Default")
      (node (ref "Q6") (pin "1") (pinfunction "S_1") (pintype "passive"))
      (node (ref "Q6") (pin "2") (pinfunction "S_2") (pintype "passive"))
      (node (ref "Q6") (pin "3") (pinfunction "S_3") (pintype "passive"))
      (node (ref "R34") (pin "2") (pinfunction "2_2") (pintype "passive"))
      (node (ref "U3") (pin "5") (pinfunction "ISEN_5") (pintype "bidirectional"))
    )
    (net (code "59") (name "Net-(U3-RT)") (class "Default")
      (node (ref "R30") (pin "1") (pinfunction "1_1") (pintype "passive"))
      (node (ref "U3") (pin "2") (pinfunction "RT_2") (pintype "bidirectional"))
    )
    (net (code "60") (name "Net-(U3-VCC)") (class "Default")
      (node (ref "C22") (pin "2") (pinfunction "2_2") (pintype "passive"))
      (node (ref "U3") (pin "7") (pinfunction "VCC_7") (pintype "bidirectional"))
    )
    (net (code "61") (name "Net-(U4-RDY{slash}*BSY)") (class "Default")
      (node (ref "R25") (pin "1") (pinfunction "1_1") (pintype "passive"))
      (node (ref "U4") (pin "5") (pinfunction "RDY/*BSY_5") (pintype "output"))
    )
    (net (code "62") (name "Net-(U5-FB)") (class "Default")
      (node (ref "R39") (pin "1") (pinfunction "1_1") (pintype "passive"))
      (node (ref "R40") (pin "2") (pinfunction "2_2") (pintype "passive"))
      (node (ref "R41") (pin "2") (pinfunction "2_2") (pintype "passive"))
      (node (ref "U5") (pin "3") (pinfunction "FB_3") (pintype "bidirectional"))
    )
    (net (code "63") (name "Net-(U5-L1)") (class "Default")
      (node (ref "L2") (pin "1") (pinfunction "1_1") (pintype "passive"))
      (node (ref "U5") (pin "8") (pinfunction "L1_8") (pintype "bidirectional"))
      (node (ref "U5") (pin "9") (pinfunction "L1_2_9") (pintype "bidirectional"))
    )
    (net (code "64") (name "Net-(U5-L2)") (class "Default")
      (node (ref "L2") (pin "2") (pinfunction "2_2") (pintype "passive"))
      (node (ref "U5") (pin "6") (pinfunction "L2_6") (pintype "bidirectional"))
      (node (ref "U5") (pin "7") (pinfunction "L2_2_7") (pintype "bidirectional"))
    )
    (net (code "65") (name "Net-(U5-VINA)") (class "Default")
      (node (ref "C20") (pin "1") (pinfunction "1_1") (pintype "passive"))
      (node (ref "U5") (pin "1") (pinfunction "VINA_1") (pintype "bidirectional"))
    )
    (net (code "66") (name "Net-(U5-VOUT)") (class "Default")
      (node (ref "C28") (pin "1") (pinfunction "1_1") (pintype "passive"))
      (node (ref "C31") (pin "1") (pinfunction "1_1") (pintype "passive"))
      (node (ref "R39") (pin "2") (pinfunction "2_2") (pintype "passive"))
      (node (ref "TEC3") (pin "2") (pinfunction "2_2") (pintype "passive"))
      (node (ref "U5") (pin "4") (pinfunction "VOUT_4") (pintype "bidirectional"))
      (node (ref "U5") (pin "5") (pinfunction "VOUT_2_5") (pintype "bidirectional"))
    )
    (net (code "67") (name "Net-(U6-PA00{slash}EINT0{slash}SERCOM1.0)") (class "Default")
      (node (ref "C8") (pin "1") (pinfunction "1_1") (pintype "passive"))
      (node (ref "U6") (pin "1") (pinfunction "PA00/EINT0/SERCOM1.0_1") (pintype "bidirectional"))
      (node (ref "X2") (pin "P$2") (pinfunction "P$2_P$2") (pintype "bidirectional"))
    )
    (net (code "68") (name "Net-(U6-PA01{slash}EINT1{slash}SERCOM1.1)") (class "Default")
      (node (ref "C6") (pin "1") (pinfunction "1_1") (pintype "passive"))
      (node (ref "U6") (pin "2") (pinfunction "PA01/EINT1/SERCOM1.1_2") (pintype "bidirectional"))
      (node (ref "X2") (pin "P$1") (pinfunction "P$1_P$1") (pintype "bidirectional"))
    )
    (net (code "69") (name "Net-(U6-PA03{slash}EINT3{slash}VREFA{slash}AIN1)") (class "Default")
      (node (ref "C7") (pin "1") (pinfunction "1_1") (pintype "passive"))
      (node (ref "U6") (pin "4") (pinfunction "PA03/EINT3/VREFA/AIN1_4") (pintype "bidirectional"))
    )
    (net (code "70") (name "Net-(U6-VDDCORE)") (class "Default")
      (node (ref "C27") (pin "1") (pinfunction "1_1") (pintype "passive"))
      (node (ref "U6") (pin "43") (pinfunction "VDDCORE_43") (pintype "power_in"))
    )
    (net (code "71") (name "Net-(U7-EN)") (class "Default")
      (node (ref "R35") (pin "2") (pinfunction "2_2") (pintype "passive"))
      (node (ref "U7") (pin "3") (pinfunction "EN_3") (pintype "input"))
    )
    (net (code "72") (name "Net-(U8-FB)") (class "Default")
      (node (ref "R52") (pin "1") (pinfunction "1_1") (pintype "passive"))
      (node (ref "R53") (pin "2") (pinfunction "2_2") (pintype "passive"))
      (node (ref "R54") (pin "2") (pinfunction "2_2") (pintype "passive"))
      (node (ref "U8") (pin "3") (pinfunction "FB_3") (pintype "bidirectional"))
    )
    (net (code "73") (name "Net-(U8-L1)") (class "Default")
      (node (ref "L4") (pin "1") (pinfunction "1_1") (pintype "passive"))
      (node (ref "U8") (pin "8") (pinfunction "L1_8") (pintype "bidirectional"))
      (node (ref "U8") (pin "9") (pinfunction "L1_2_9") (pintype "bidirectional"))
    )
    (net (code "74") (name "Net-(U8-L2)") (class "Default")
      (node (ref "L4") (pin "2") (pinfunction "2_2") (pintype "passive"))
      (node (ref "U8") (pin "6") (pinfunction "L2_6") (pintype "bidirectional"))
      (node (ref "U8") (pin "7") (pinfunction "L2_2_7") (pintype "bidirectional"))
    )
    (net (code "75") (name "Net-(U8-VINA)") (class "Default")
      (node (ref "C37") (pin "1") (pinfunction "1_1") (pintype "passive"))
      (node (ref "U8") (pin "1") (pinfunction "VINA_1") (pintype "bidirectional"))
    )
    (net (code "76") (name "Net-(U8-VOUT)") (class "Default")
      (node (ref "C42") (pin "1") (pinfunction "1_1") (pintype "passive"))
      (node (ref "C43") (pin "1") (pinfunction "1_1") (pintype "passive"))
      (node (ref "R52") (pin "2") (pinfunction "2_2") (pintype "passive"))
      (node (ref "TEC2") (pin "2") (pinfunction "2_2") (pintype "passive"))
      (node (ref "U8") (pin "4") (pinfunction "VOUT_4") (pintype "bidirectional"))
      (node (ref "U8") (pin "5") (pinfunction "VOUT_2_5") (pintype "bidirectional"))
    )
    (net (code "77") (name "Net-(U9-A0)") (class "Default")
      (node (ref "R46") (pin "2") (pinfunction "2_2") (pintype "passive"))
      (node (ref "U9") (pin "7") (pinfunction "A0_7") (pintype "bidirectional"))
    )
    (net (code "78") (name "Net-(U9-A1)") (class "Default")
      (node (ref "R49") (pin "2") (pinfunction "2_2") (pintype "passive"))
      (node (ref "U9") (pin "8") (pinfunction "A1_8") (pintype "bidirectional"))
    )
    (net (code "79") (name "Net-(U9-{slash}INT)") (class "Default")
      (node (ref "R44") (pin "1") (pinfunction "1_1") (pintype "passive"))
      (node (ref "U9") (pin "6") (pinfunction "/INT_6") (pintype "bidirectional"))
    )
    (net (code "80") (name "Net-(U10-A0)") (class "Default")
      (node (ref "R48") (pin "2") (pinfunction "2_2") (pintype "passive"))
      (node (ref "U10") (pin "7") (pinfunction "A0_7") (pintype "bidirectional"))
    )
    (net (code "81") (name "Net-(U10-A1)") (class "Default")
      (node (ref "R51") (pin "2") (pinfunction "2_2") (pintype "passive"))
      (node (ref "U10") (pin "8") (pinfunction "A1_8") (pintype "bidirectional"))
    )
    (net (code "82") (name "Net-(U10-{slash}INT)") (class "Default")
      (node (ref "R45") (pin "1") (pinfunction "1_1") (pintype "passive"))
      (node (ref "U10") (pin "6") (pinfunction "/INT_6") (pintype "bidirectional"))
    )
    (net (code "83") (name "Net-(U11-FB)") (class "Default")
      (node (ref "R73") (pin "1") (pinfunction "1_1") (pintype "passive"))
      (node (ref "R74") (pin "2") (pinfunction "2_2") (pintype "passive"))
      (node (ref "R75") (pin "2") (pinfunction "2_2") (pintype "passive"))
      (node (ref "U11") (pin "3") (pinfunction "FB_3") (pintype "bidirectional"))
    )
    (net (code "84") (name "Net-(U11-L1)") (class "Default")
      (node (ref "L5") (pin "1") (pinfunction "1_1") (pintype "passive"))
      (node (ref "U11") (pin "8") (pinfunction "L1_8") (pintype "bidirectional"))
      (node (ref "U11") (pin "9") (pinfunction "L1_2_9") (pintype "bidirectional"))
    )
    (net (code "85") (name "Net-(U11-L2)") (class "Default")
      (node (ref "L5") (pin "2") (pinfunction "2_2") (pintype "passive"))
      (node (ref "U11") (pin "6") (pinfunction "L2_6") (pintype "bidirectional"))
      (node (ref "U11") (pin "7") (pinfunction "L2_2_7") (pintype "bidirectional"))
    )
    (net (code "86") (name "Net-(U11-VINA)") (class "Default")
      (node (ref "C46") (pin "1") (pinfunction "1_1") (pintype "passive"))
      (node (ref "U11") (pin "1") (pinfunction "VINA_1") (pintype "bidirectional"))
    )
    (net (code "87") (name "Net-(U11-VOUT)") (class "Default")
      (node (ref "C47") (pin "1") (pinfunction "1_1") (pintype "passive"))
      (node (ref "C48") (pin "1") (pinfunction "1_1") (pintype "passive"))
      (node (ref "R73") (pin "2") (pinfunction "2_2") (pintype "passive"))
      (node (ref "TEC1") (pin "2") (pinfunction "2_2") (pintype "passive"))
      (node (ref "U11") (pin "4") (pinfunction "VOUT_4") (pintype "bidirectional"))
      (node (ref "U11") (pin "5") (pinfunction "VOUT_2_5") (pintype "bidirectional"))
    )
    (net (code "88") (name "Net-(U12-ILIM)") (class "Default")
      (node (ref "R82") (pin "1") (pinfunction "1_1") (pintype "passive"))
      (node (ref "U12") (pin "4") (pinfunction "ILIM_4") (pintype "input"))
    )
    (net (code "89") (name "Net-(U12-IN1)") (class "Default")
      (node (ref "R81") (pin "2") (pinfunction "2_2") (pintype "passive"))
      (node (ref "U12") (pin "3") (pinfunction "IN1_3") (pintype "input"))
    )
    (net (code "90") (name "Net-(U12-IN2)") (class "Default")
      (node (ref "R80") (pin "2") (pinfunction "2_2") (pintype "passive"))
      (node (ref "U12") (pin "2") (pinfunction "IN2_2") (pintype "input"))
    )
    (net (code "91") (name "Net-(U12-OUT1)") (class "Default")
      (node (ref "TEC5") (pin "2") (pinfunction "2_2") (pintype "passive"))
      (node (ref "U12") (pin "6") (pinfunction "OUT1_6") (pintype "output"))
    )
    (net (code "92") (name "Net-(U12-OUT2)") (class "Default")
      (node (ref "TEC5") (pin "1") (pinfunction "1_1") (pintype "passive"))
      (node (ref "U12") (pin "8") (pinfunction "OUT2_8") (pintype "output"))
    )
    (net (code "93") (name "Net-(U12-VM)") (class "Default")
      (node (ref "C50") (pin "1") (pinfunction "1_1") (pintype "passive"))
      (node (ref "C51") (pin "+") (pinfunction "+_+") (pintype "passive"))
      (node (ref "SJ1") (pin "2") (pinfunction "2_2") (pintype "passive"))
      (node (ref "U12") (pin "5") (pinfunction "VM_5") (pintype "power_in"))
    )
    (net (code "94") (name "PWM_0") (class "Default")
      (node (ref "R28") (pin "1") (pinfunction "1_1") (pintype "passive"))
      (node (ref "R80") (pin "1") (pinfunction "1_1") (pintype "passive"))
      (node (ref "U6") (pin "7") (pinfunction "PB08/I8/AIN2/SERCOM4.0_7") (pintype "bidirectional"))
    )
    (net (code "95") (name "PWM_1") (class "Default")
      (node (ref "R43") (pin "1") (pinfunction "1_1") (pintype "passive"))
      (node (ref "R81") (pin "1") (pinfunction "1_1") (pintype "passive"))
      (node (ref "U6") (pin "8") (pinfunction "PB09/I9/AIN3/SERCOM4.1_8") (pintype "bidirectional"))
    )
    (net (code "96") (name "PWM_2") (class "Default")
      (node (ref "R56") (pin "1") (pinfunction "1_1") (pintype "passive"))
      (node (ref "U6") (pin "19") (pinfunction "PB10/I10/SERCOM4.2/I2SMC_19") (pintype "bidirectional"))
    )
    (net (code "97") (name "PWM_3") (class "Default")
      (node (ref "R76") (pin "1") (pinfunction "1_1") (pintype "passive"))
      (node (ref "U6") (pin "20") (pinfunction "PB11/I11/SERCOM4.3/I2SCL_20") (pintype "bidirectional"))
    )
    (net (code "98") (name "SCK") (class "Default")
      (node (ref "SD1") (pin "5") (pinfunction "SCLK_5") (pintype "input"))
      (node (ref "TP15") (pin "P$1") (pinfunction "P$1_P$1") (pintype "bidirectional"))
      (node (ref "U6") (pin "26") (pinfunction "PA17/I2C/I1/SERCOM1+3.1_26") (pintype "bidirectional"))
    )
    (net (code "99") (name "SCL_1") (class "Default")
      (node (ref "R47") (pin "1") (pinfunction "1_1") (pintype "passive"))
      (node (ref "TP8") (pin "P$1") (pinfunction "P$1_P$1") (pintype "bidirectional"))
      (node (ref "U10") (pin "3") (pinfunction "SCL_3") (pintype "bidirectional"))
      (node (ref "U6") (pin "32") (pinfunction "PA23/I2C/I7/SERCOM3+5.1/SOF_32") (pintype "bidirectional"))
      (node (ref "U9") (pin "3") (pinfunction "SCL_3") (pintype "bidirectional"))
    )
    (net (code "100") (name "SCL_2") (class "Default")
      (node (ref "Q3") (pin "2") (pinfunction "2_2") (pintype "bidirectional"))
      (node (ref "R13") (pin "2") (pinfunction "2_2") (pintype "passive"))
      (node (ref "R8") (pin "1") (pinfunction "1_1") (pintype "passive"))
      (node (ref "TP10") (pin "P$1") (pinfunction "P$1_P$1") (pintype "bidirectional"))
      (node (ref "U6") (pin "22") (pinfunction "PA13/I13/I2C/SERCOM2+4.1_22") (pintype "bidirectional"))
    )
    (net (code "101") (name "SCL_2_H") (class "Default")
      (node (ref "Q3") (pin "3") (pinfunction "3_3") (pintype "bidirectional"))
      (node (ref "R14") (pin "2") (pinfunction "2_2") (pintype "passive"))
      (node (ref "R19") (pin "1") (pinfunction "1_1") (pintype "passive"))
    )
    (net (code "102") (name "SCL_3") (class "Default")
      (node (ref "Q2") (pin "2") (pinfunction "2_2") (pintype "bidirectional"))
      (node (ref "R7") (pin "1") (pinfunction "1_1") (pintype "passive"))
      (node (ref "TP12") (pin "P$1") (pinfunction "P$1_P$1") (pintype "bidirectional"))
      (node (ref "U6") (pin "14") (pinfunction "PA09/I2C/I9/AIN17/SERCOM0+2.1/I2SMC_14") (pintype "bidirectional"))
    )
    (net (code "103") (name "SCL_3_H") (class "Default")
      (node (ref "Q2") (pin "3") (pinfunction "3_3") (pintype "bidirectional"))
      (node (ref "R16") (pin "1") (pinfunction "1_1") (pintype "passive"))
      (node (ref "U4") (pin "2") (pinfunction "SCL_2") (pintype "input"))
    )
    (net (code "104") (name "SDA_1") (class "Default")
      (node (ref "R50") (pin "1") (pinfunction "1_1") (pintype "passive"))
      (node (ref "TP7") (pin "P$1") (pinfunction "P$1_P$1") (pintype "bidirectional"))
      (node (ref "U10") (pin "2") (pinfunction "SDA_2") (pintype "bidirectional"))
      (node (ref "U6") (pin "31") (pinfunction "PA22/I2C/I6/SERCOM3+5.0_31") (pintype "bidirectional"))
      (node (ref "U9") (pin "2") (pinfunction "SDA_2") (pintype "bidirectional"))
    )
    (net (code "105") (name "SDA_2") (class "Default")
      (node (ref "Q5") (pin "2") (pinfunction "2_2") (pintype "bidirectional"))
      (node (ref "R11") (pin "2") (pinfunction "2_2") (pintype "passive"))
      (node (ref "R6") (pin "1") (pinfunction "1_1") (pintype "passive"))
      (node (ref "TP9") (pin "P$1") (pinfunction "P$1_P$1") (pintype "bidirectional"))
      (node (ref "U6") (pin "21") (pinfunction "PA12/I12/I2C/SERCOM2+4.0_21") (pintype "bidirectional"))
    )
    (net (code "106") (name "SDA_2_H") (class "Default")
      (node (ref "Q5") (pin "3") (pinfunction "3_3") (pintype "bidirectional"))
      (node (ref "R12") (pin "2") (pinfunction "2_2") (pintype "passive"))
      (node (ref "R15") (pin "1") (pinfunction "1_1") (pintype "passive"))
    )
    (net (code "107") (name "SDA_3") (class "Default")
      (node (ref "Q4") (pin "2") (pinfunction "2_2") (pintype "bidirectional"))
      (node (ref "R4") (pin "1") (pinfunction "1_1") (pintype "passive"))
      (node (ref "TP11") (pin "P$1") (pinfunction "P$1_P$1") (pintype "bidirectional"))
      (node (ref "U6") (pin "13") (pinfunction "PA08/I2C/AIN16/SERCOM0+2.0/I2SD1_13") (pintype "bidirectional"))
    )
    (net (code "108") (name "SDA_3_H") (class "Default")
      (node (ref "Q4") (pin "3") (pinfunction "3_3") (pintype "bidirectional"))
      (node (ref "R10") (pin "1") (pinfunction "1_1") (pintype "passive"))
      (node (ref "U4") (pin "3") (pinfunction "SDA_3") (pintype "bidirectional"))
    )
    (net (code "109") (name "SERIAL_NUM_1W") (class "Default")
      (node (ref "CHIP0") (pin "5") (pinfunction "5_5") (pintype "passive"))
      (node (ref "CHIP1") (pin "5") (pinfunction "5_5") (pintype "passive"))
      (node (ref "CHIP2") (pin "5") (pinfunction "5_5") (pintype "passive"))
      (node (ref "CHIP3") (pin "5") (pinfunction "5_5") (pintype "passive"))
      (node (ref "CHIP4") (pin "5") (pinfunction "5_5") (pintype "passive"))
      (node (ref "CHIP5") (pin "5") (pinfunction "5_5") (pintype "passive"))
      (node (ref "CHIP6") (pin "5") (pinfunction "5_5") (pintype "passive"))
      (node (ref "CHIP7") (pin "5") (pinfunction "5_5") (pintype "passive"))
      (node (ref "R21") (pin "1") (pinfunction "1_1") (pintype "passive"))
      (node (ref "U6") (pin "29") (pinfunction "PA20/I4/SERCOM3+5.2/I2SSC_29") (pintype "bidirectional"))
    )
    (net (code "110") (name "SWCLK") (class "Default")
      (node (ref "DEBUG") (pin "4") (pinfunction "SWDCLK/TCK_4") (pintype "bidirectional"))
      (node (ref "R22") (pin "1") (pinfunction "1_1") (pintype "passive"))
      (node (ref "TP18") (pin "P$1") (pinfunction "P$1_P$1") (pintype "bidirectional"))
      (node (ref "U6") (pin "45") (pinfunction "PA30/I10/SECOM1.2/SWCLK_45") (pintype "bidirectional"))
    )
    (net (code "111") (name "SWDIO") (class "Default")
      (node (ref "DEBUG") (pin "2") (pinfunction "SWDIO/TMS_2") (pintype "bidirectional"))
      (node (ref "TP17") (pin "P$1") (pinfunction "P$1_P$1") (pintype "bidirectional"))
      (node (ref "U6") (pin "46") (pinfunction "PA31/I11/SECOM1.3/SWDIO_46") (pintype "bidirectional"))
    )
    (net (code "112") (name "TEC_EN") (class "Default")
      (node (ref "Q1") (pin "1") (pinfunction "G_1") (pintype "passive"))
      (node (ref "U6") (pin "10") (pinfunction "PA05/EINT5/AIN5/SERCOM0.1_10") (pintype "bidirectional"))
    )
    (net (code "113") (name "USBD_N") (class "Default")
      (node (ref "U6") (pin "33") (pinfunction "PA24/I12/SERCOM3+5.2/D-_33") (pintype "bidirectional"))
      (node (ref "USB") (pin "D-") (pinfunction "D-_D-") (pintype "bidirectional"))
    )
    (net (code "114") (name "USBD_P") (class "Default")
      (node (ref "U6") (pin "34") (pinfunction "PA25/I13/SERCOM3+5.3/D+_34") (pintype "bidirectional"))
      (node (ref "USB") (pin "D+") (pinfunction "D+_D+") (pintype "bidirectional"))
    )
    (net (code "115") (name "VDAC_0") (class "Default")
      (node (ref "R29") (pin "1") (pinfunction "1_1") (pintype "passive"))
      (node (ref "U4") (pin "6") (pinfunction "VOUTA_6") (pintype "output"))
    )
    (net (code "116") (name "VDAC_1") (class "Default")
      (node (ref "R42") (pin "1") (pinfunction "1_1") (pintype "passive"))
      (node (ref "U4") (pin "7") (pinfunction "VOUTB_7") (pintype "output"))
    )
    (net (code "117") (name "VDAC_2") (class "Default")
      (node (ref "R58") (pin "1") (pinfunction "1_1") (pintype "passive"))
      (node (ref "U4") (pin "8") (pinfunction "VOUTC_8") (pintype "output"))
    )
    (net (code "118") (name "VDAC_3") (class "Default")
      (node (ref "R77") (pin "1") (pinfunction "1_1") (pintype "passive"))
      (node (ref "U4") (pin "9") (pinfunction "VOUTD_9") (pintype "output"))
    )
    (net (code "119") (name "VREG_IN") (class "Default")
      (node (ref "C13") (pin "1") (pinfunction "1_1") (pintype "passive"))
      (node (ref "C9") (pin "1") (pinfunction "1_1") (pintype "passive"))
      (node (ref "D1") (pin "C") (pinfunction "C_C") (pintype "passive"))
      (node (ref "R35") (pin "1") (pinfunction "1_1") (pintype "passive"))
      (node (ref "U2") (pin "3") (pinfunction "IN_3") (pintype "input"))
      (node (ref "U7") (pin "1") (pinfunction "IN_1") (pintype "power_in"))
    )
    (net (code "120") (name "VUSB") (class "Default")
      (node (ref "USB") (pin "VBUS") (pinfunction "VBUS_VBUS") (pintype "power_in"))
    )
    (net (code "121") (name "unconnected-(DEBUG-GNDDTCT-Pad9)") (class "Default")
      (node (ref "DEBUG") (pin "9") (pinfunction "GNDDTCT_9") (pintype "bidirectional"))
    )
    (net (code "122") (name "unconnected-(DEBUG-KEY-Pad7)") (class "Default")
      (node (ref "DEBUG") (pin "7") (pinfunction "KEY_7") (pintype "bidirectional"))
    )
    (net (code "123") (name "unconnected-(DEBUG-NC{slash}TDI-Pad8)") (class "Default")
      (node (ref "DEBUG") (pin "8") (pinfunction "NC/TDI_8") (pintype "bidirectional"))
    )
    (net (code "124") (name "unconnected-(DEBUG-SWO{slash}TDO-Pad6)") (class "Default")
      (node (ref "DEBUG") (pin "6") (pinfunction "SWO/TDO_6") (pintype "bidirectional"))
    )
    (net (code "125") (name "unconnected-(SD1-CARD_DETECT1-PadCD2)") (class "Default")
      (node (ref "SD1") (pin "CD2") (pinfunction "CARD_DETECT1_CD2") (pintype "passive"))
    )
    (net (code "126") (name "unconnected-(SD1-DAT1-Pad8)") (class "Default")
      (node (ref "SD1") (pin "8") (pinfunction "DAT1_8") (pintype "bidirectional"))
    )
    (net (code "127") (name "unconnected-(SD1-DAT2-Pad1)") (class "Default")
      (node (ref "SD1") (pin "1") (pinfunction "DAT2_1") (pintype "bidirectional"))
    )
    (net (code "128") (name "unconnected-(U1-PG-Pad14)") (class "Default")
      (node (ref "U1") (pin "14") (pinfunction "PG_14") (pintype "bidirectional"))
    )
    (net (code "129") (name "unconnected-(U5-PG-Pad14)") (class "Default")
      (node (ref "U5") (pin "14") (pinfunction "PG_14") (pintype "bidirectional"))
    )
    (net (code "130") (name "unconnected-(U6-PA28{slash}I8-Pad41)") (class "Default")
      (node (ref "U6") (pin "41") (pinfunction "PA28/I8_41") (pintype "bidirectional"))
    )
    (net (code "131") (name "unconnected-(U7-P4-Pad4)") (class "Default")
      (node (ref "U7") (pin "4") (pinfunction "P4_4") (pintype "bidirectional"))
    )
    (net (code "132") (name "unconnected-(U8-PG-Pad14)") (class "Default")
      (node (ref "U8") (pin "14") (pinfunction "PG_14") (pintype "bidirectional"))
    )
    (net (code "133") (name "unconnected-(U9-VREF-Pad1)") (class "Default")
      (node (ref "U9") (pin "1") (pinfunction "VREF_1") (pintype "bidirectional"))
    )
    (net (code "134") (name "unconnected-(U10-VREF-Pad1)") (class "Default")
      (node (ref "U10") (pin "1") (pinfunction "VREF_1") (pintype "bidirectional"))
    )
    (net (code "135") (name "unconnected-(U11-PG-Pad14)") (class "Default")
      (node (ref "U11") (pin "14") (pinfunction "PG_14") (pintype "bidirectional"))
    )
    (net (code "136") (name "unconnected-(USB-PadID)") (class "Default")
      (node (ref "USB") (pin "ID") (pinfunction "ID_ID") (pintype "bidirectional"))
    )
    (net (code "137") (name "{slash}RESET") (class "Default")
      (node (ref "C5") (pin "2") (pinfunction "2_2") (pintype "passive"))
      (node (ref "DEBUG") (pin "10") (pinfunction "~{RESET}_10") (pintype "bidirectional"))
      (node (ref "R17") (pin "1") (pinfunction "1_1") (pintype "passive"))
      (node (ref "R18") (pin "2") (pinfunction "2_2") (pintype "passive"))
      (node (ref "TP19") (pin "P$1") (pinfunction "P$1_P$1") (pintype "bidirectional"))
      (node (ref "U6") (pin "40") (pinfunction "~{RESETN}_40") (pintype "input"))
    )
    (net (code "138") (name "{slash}SS") (class "Default")
      (node (ref "R79") (pin "1") (pinfunction "1_1") (pintype "passive"))
      (node (ref "SD1") (pin "2") (pinfunction "CS_2") (pintype "input"))
      (node (ref "TP16") (pin "P$1") (pinfunction "P$1_P$1") (pintype "bidirectional"))
      (node (ref "U6") (pin "27") (pinfunction "PA18/I2/SERCOM1+3.2_27") (pintype "bidirectional"))
    )
  )
)
